# Digitalizador_RPi.net
KiCad netlist of a schematic drawn in Altium Designer
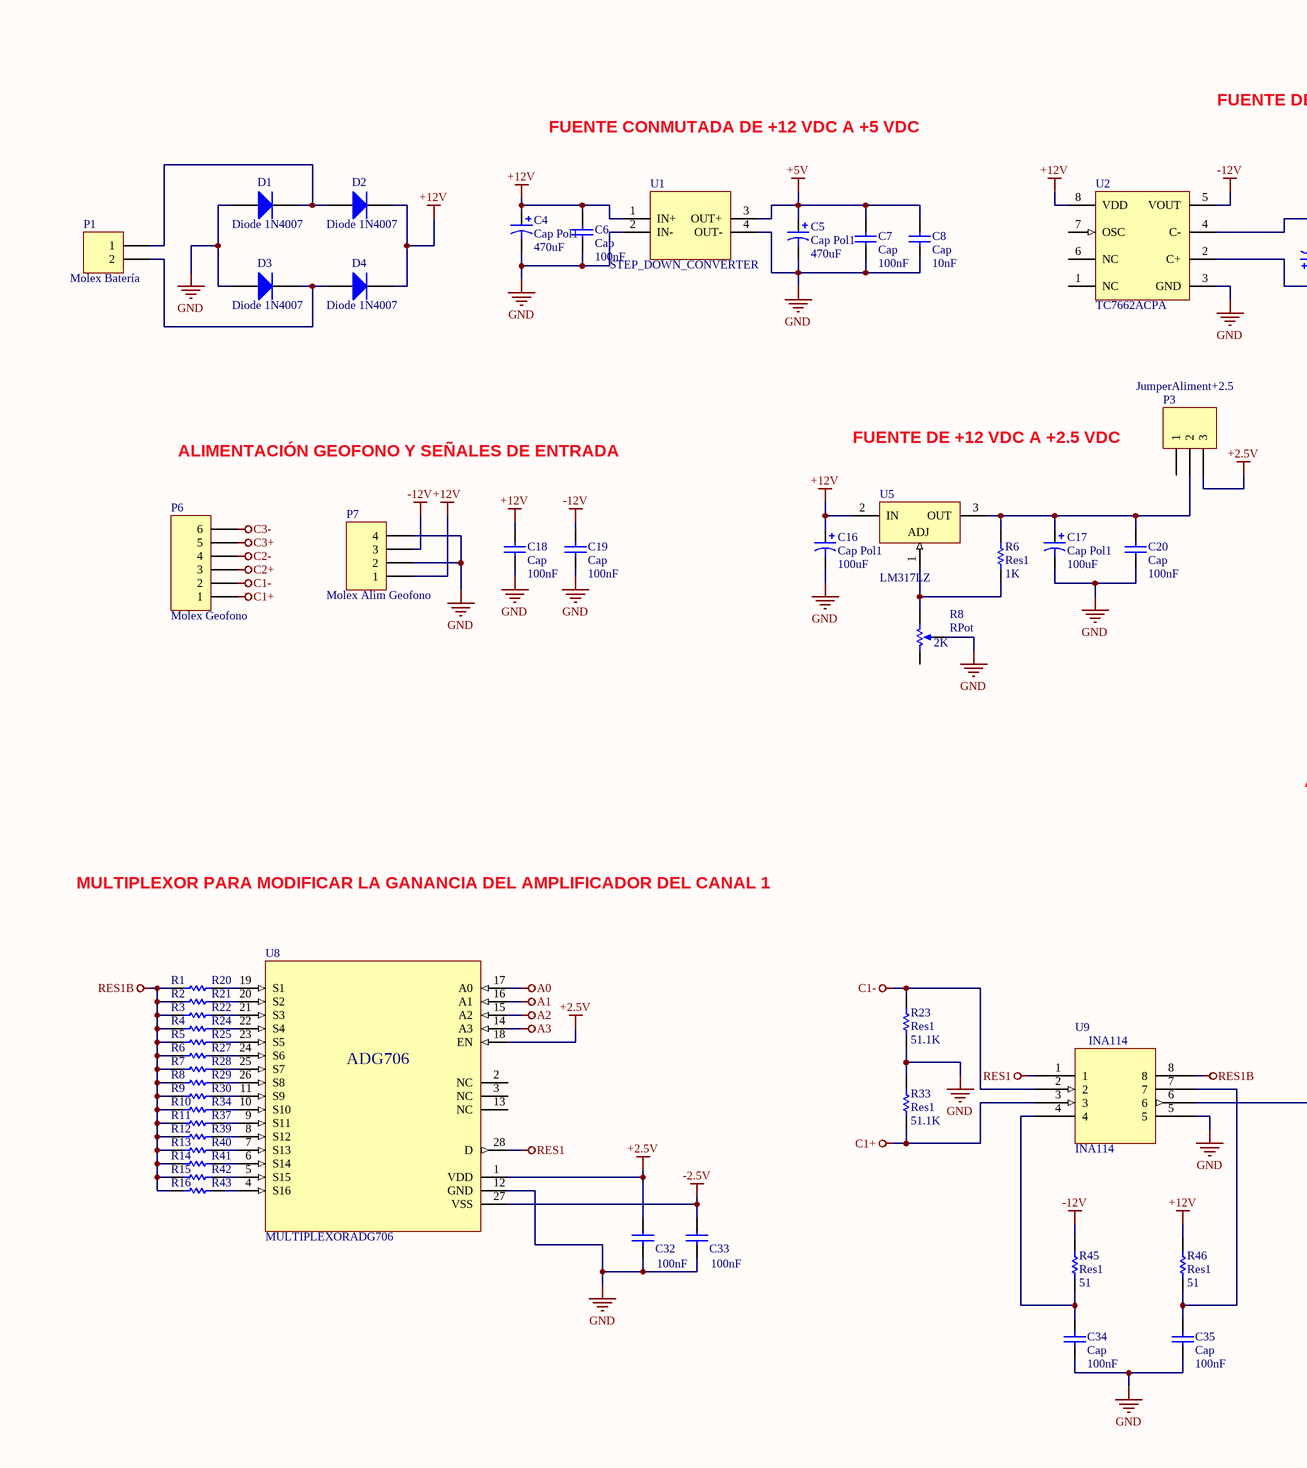
[diagram p0: Digitalizador_RPi.SchDoc, top left]
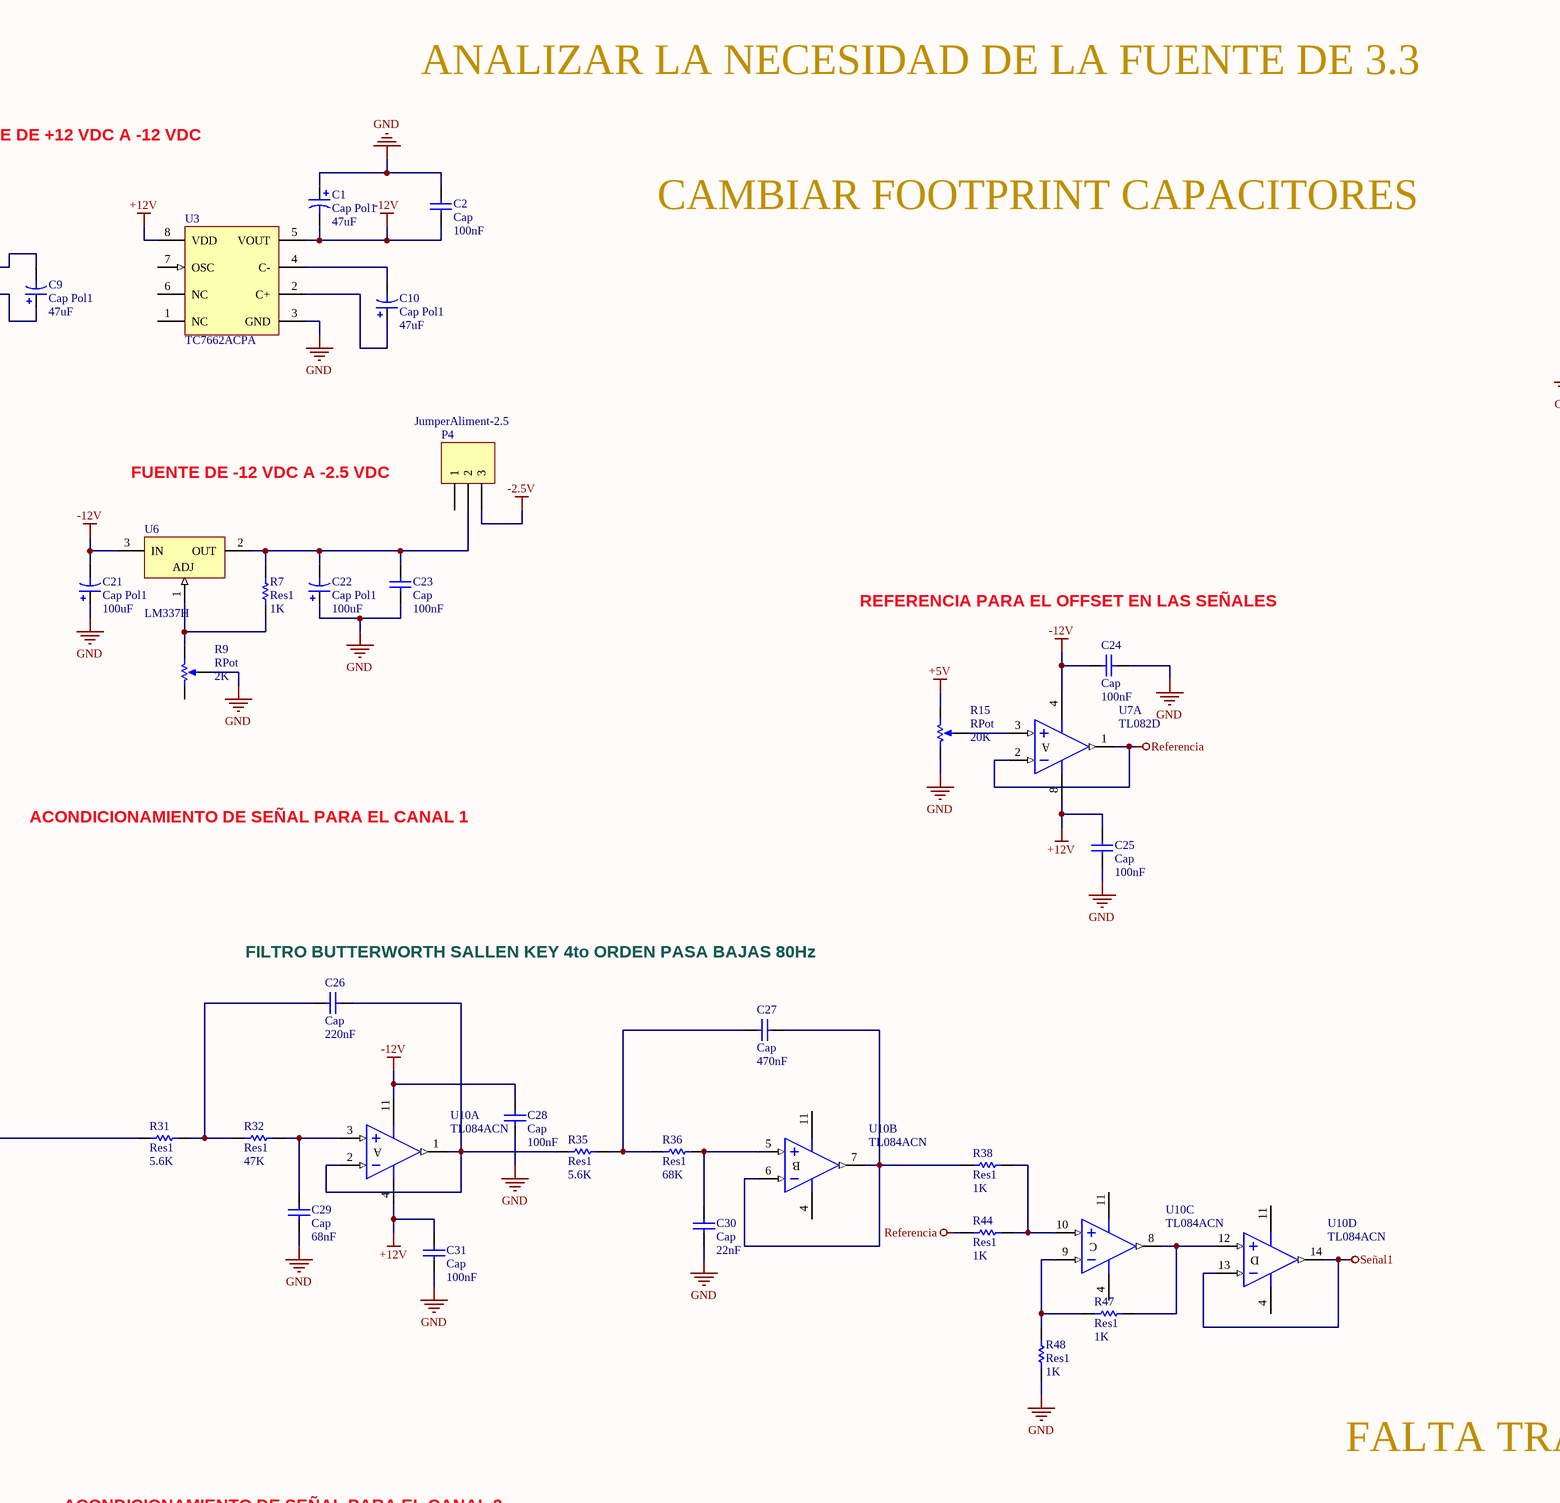
[diagram p1: Digitalizador_RPi.SchDoc, top middle]
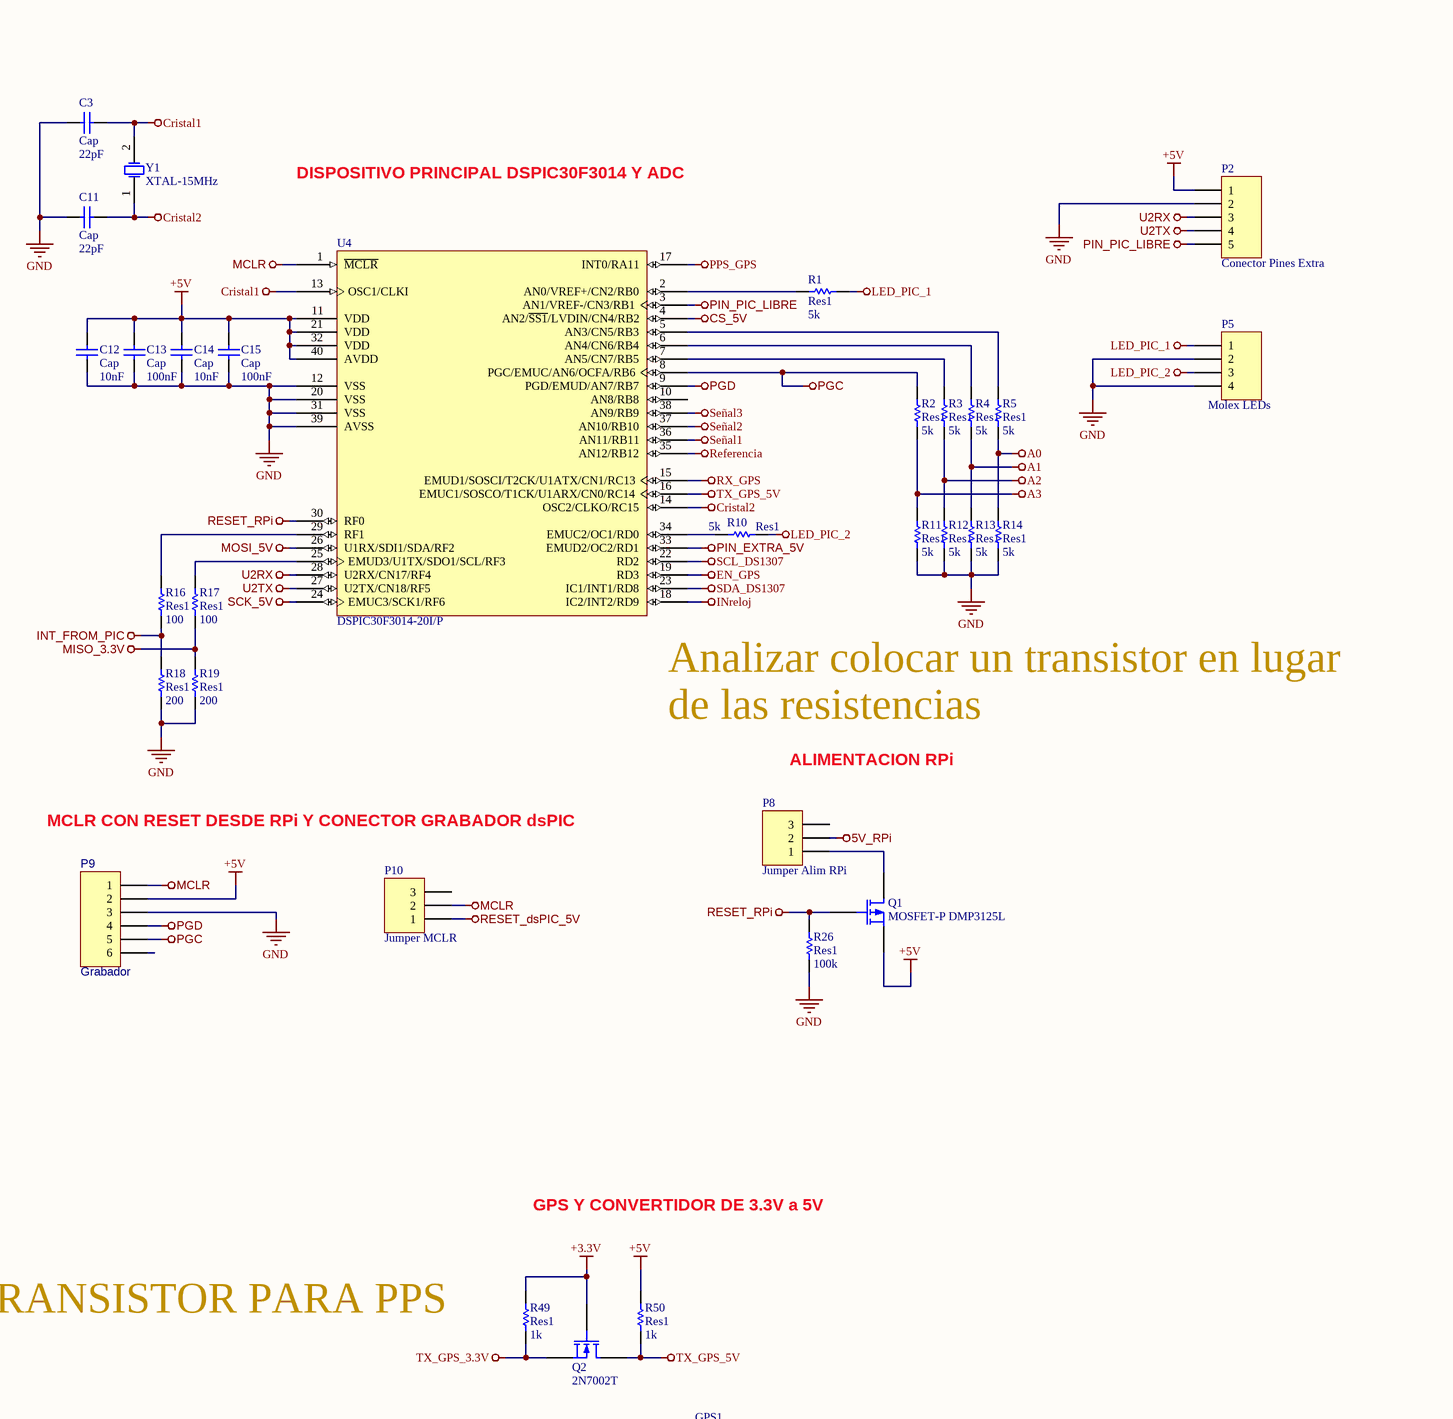
[diagram p2: Digitalizador_RPi.SchDoc, top right]
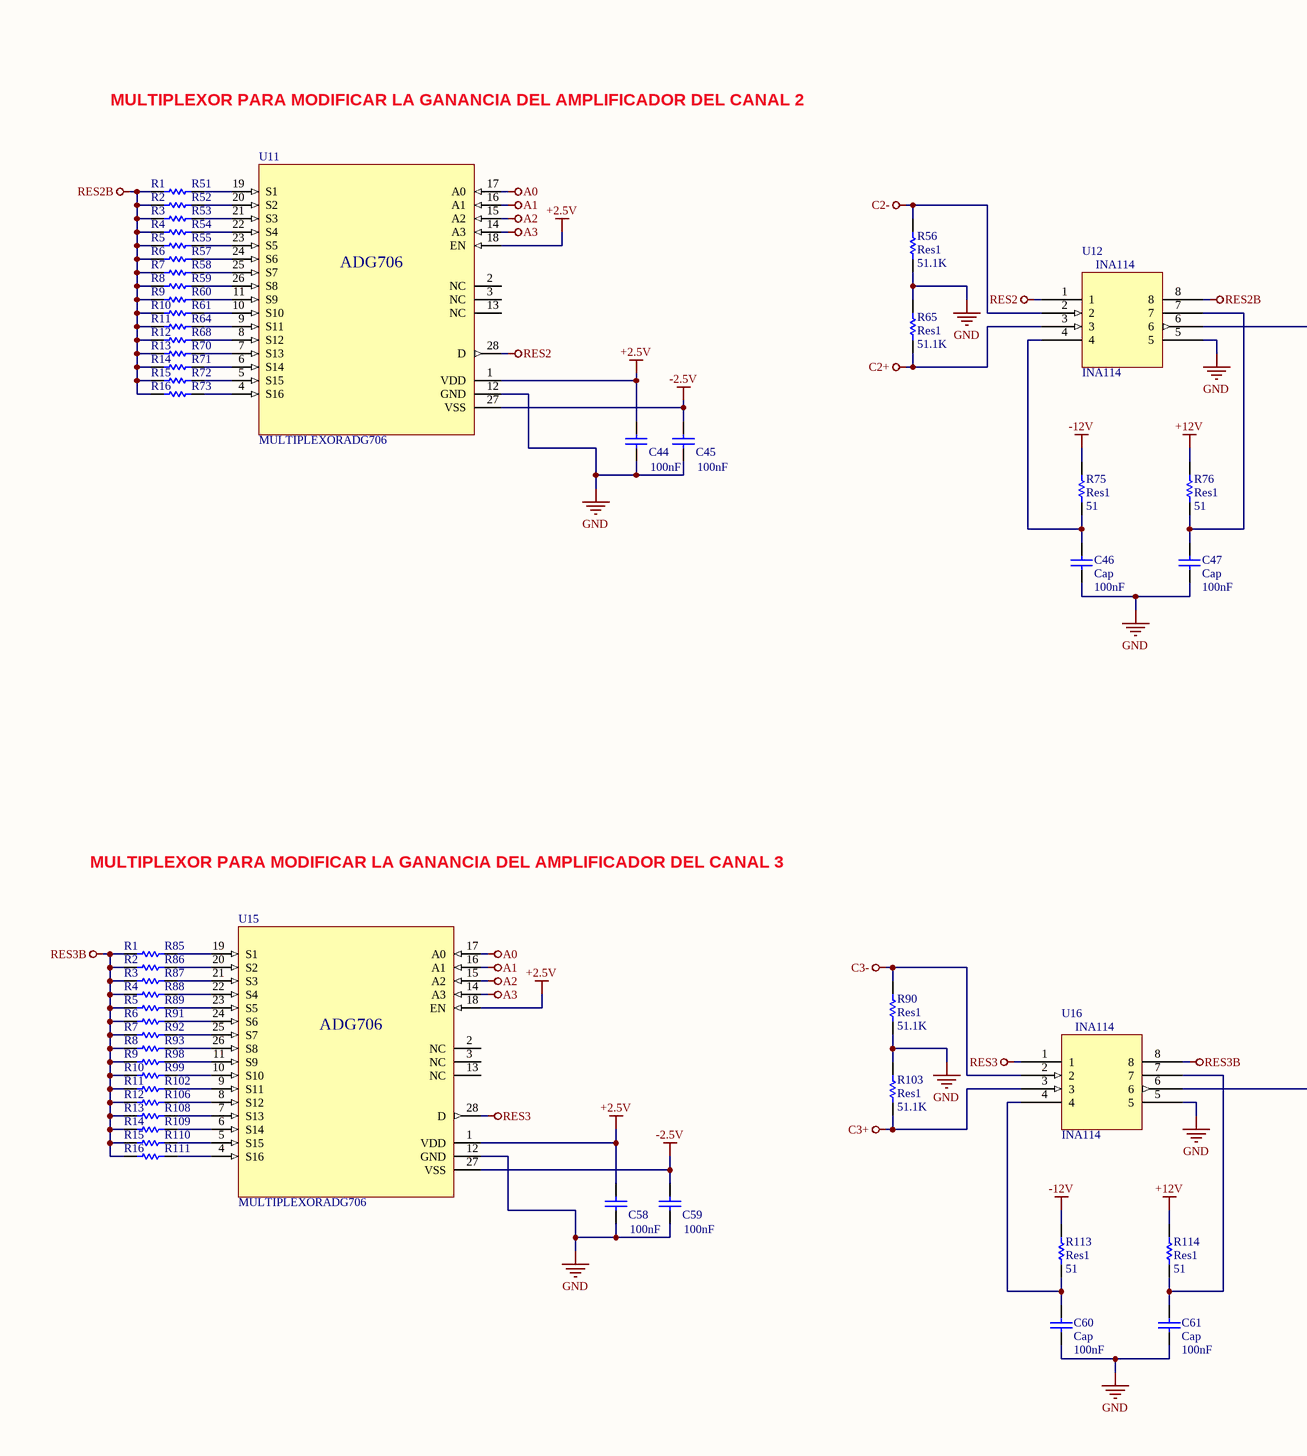
[diagram p3: Digitalizador_RPi.SchDoc, bottom left]
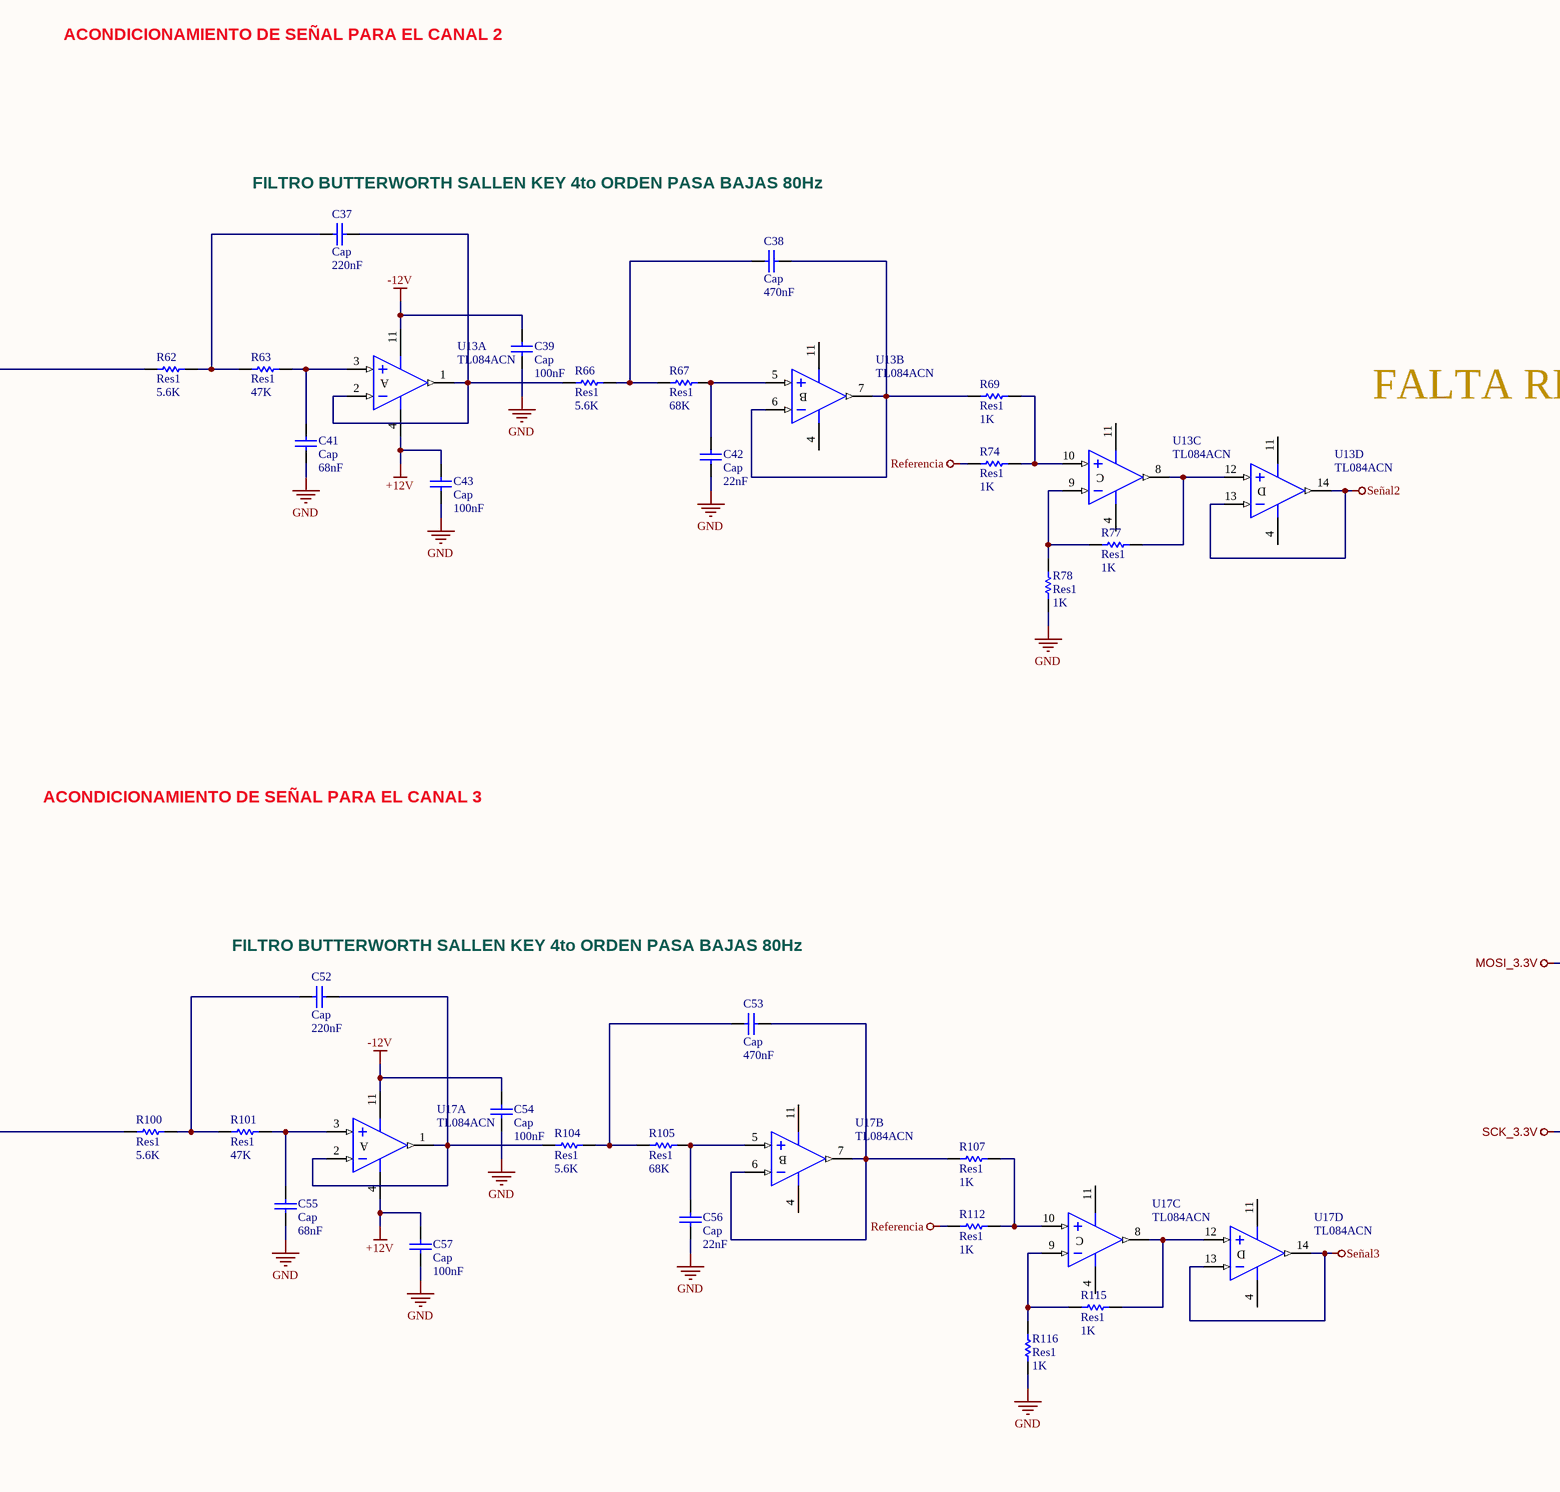
[diagram p4: Digitalizador_RPi.SchDoc, bottom middle]
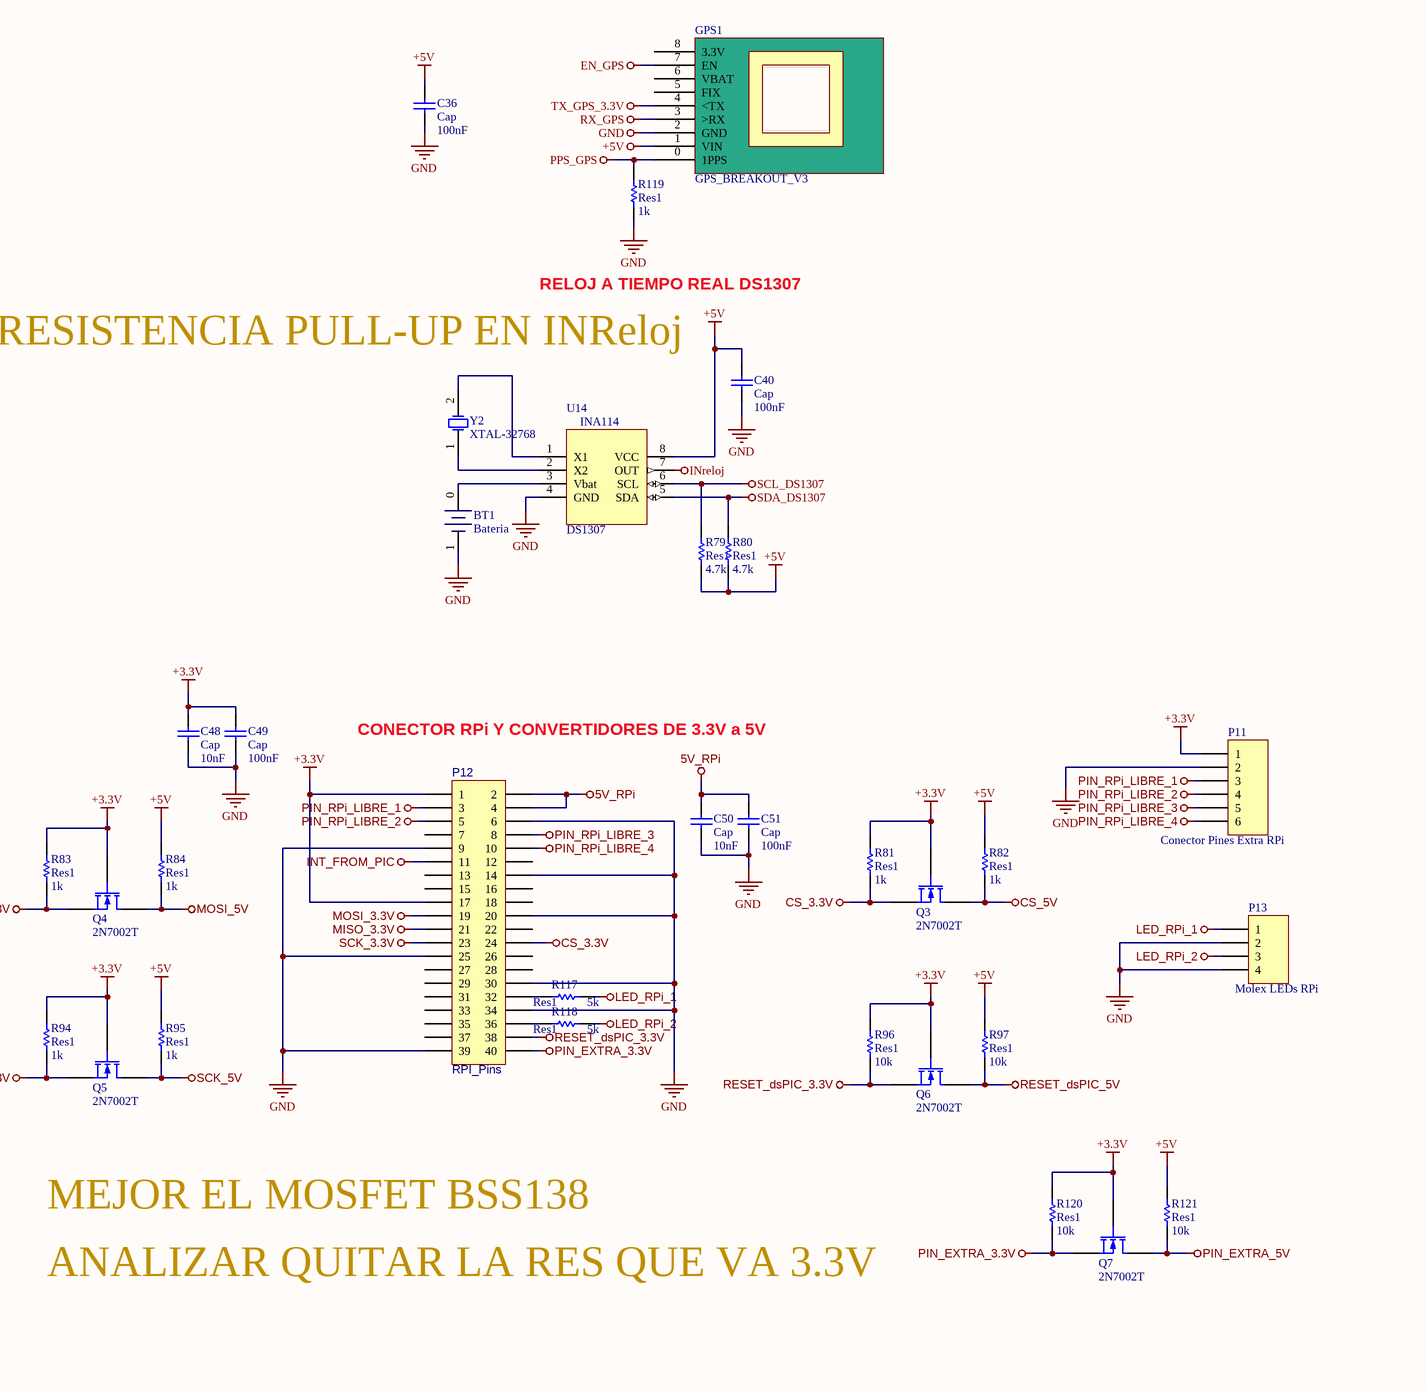
[diagram p5: Digitalizador_RPi.SchDoc, bottom right]

(export (version "E")
  (design (tool "Eeschema 10.0.6"))
  (components
    (comp (ref "BT1")
      (value "Bateria")
      (footprint "Bateria-DS1307")
      (libsource (lib "Libreria RSA") (part "BateriaDS1307"))
    )
    (comp (ref "C1")
      (value "Cap Pol1")
      (footprint "CAP_5.5MM")
      (description "Polarized Capacitor (Radial)")
      (fields (field (name "ALTIUM_VALUE") "47uF") (field (name "PUBLISHER") "Altium Limited"))
      (libsource (lib "Miscellaneous Devices") (part "Cap Pol1"))
    )
    (comp (ref "C2")
      (value "Cap")
      (footprint "0603")
      (description "Capacitor")
      (fields (field (name "ALTIUM_VALUE") "100nF") (field (name "PUBLISHER") "Altium Limited"))
      (libsource (lib "Miscellaneous Devices") (part "Cap"))
    )
    (comp (ref "C3")
      (value "Cap")
      (footprint "Resistencias:0603")
      (description "Capacitor")
      (fields (field (name "ALTIUM_VALUE") "22pF") (field (name "PUBLISHER") "Altium Limited"))
      (libsource (lib "Miscellaneous Devices") (part "Cap"))
    )
    (comp (ref "C4")
      (value "Cap Pol1")
      (footprint "CAP_8.5mm")
      (description "Polarized Capacitor (Radial)")
      (fields (field (name "ALTIUM_VALUE") "470uF") (field (name "PUBLISHER") "Altium Limited"))
      (libsource (lib "Miscellaneous Devices") (part "Cap Pol1"))
    )
    (comp (ref "C5")
      (value "Cap Pol1")
      (footprint "CAP_8.5mm")
      (description "Polarized Capacitor (Radial)")
      (fields (field (name "ALTIUM_VALUE") "470uF") (field (name "PUBLISHER") "Altium Limited"))
      (libsource (lib "Miscellaneous Devices") (part "Cap Pol1"))
    )
    (comp (ref "C6")
      (value "Cap")
      (footprint "0603")
      (description "Capacitor")
      (fields (field (name "ALTIUM_VALUE") "100nF") (field (name "PUBLISHER") "Altium Limited"))
      (libsource (lib "Miscellaneous Devices") (part "Cap"))
    )
    (comp (ref "C7")
      (value "Cap")
      (footprint "0603")
      (description "Capacitor")
      (fields (field (name "ALTIUM_VALUE") "100nF") (field (name "PUBLISHER") "Altium Limited"))
      (libsource (lib "Miscellaneous Devices") (part "Cap"))
    )
    (comp (ref "C8")
      (value "Cap")
      (footprint "0603")
      (description "Capacitor")
      (fields (field (name "ALTIUM_VALUE") "10nF") (field (name "PUBLISHER") "Altium Limited"))
      (libsource (lib "Miscellaneous Devices") (part "Cap"))
    )
    (comp (ref "C9")
      (value "Cap Pol1")
      (footprint "CAP_5.5MM")
      (description "Polarized Capacitor (Radial)")
      (fields (field (name "ALTIUM_VALUE") "47uF") (field (name "PUBLISHER") "Altium Limited"))
      (libsource (lib "Miscellaneous Devices") (part "Cap Pol1"))
    )
    (comp (ref "C10")
      (value "Cap Pol1")
      (footprint "CAP_5.5MM")
      (description "Polarized Capacitor (Radial)")
      (fields (field (name "ALTIUM_VALUE") "47uF") (field (name "PUBLISHER") "Altium Limited"))
      (libsource (lib "Miscellaneous Devices") (part "Cap Pol1"))
    )
    (comp (ref "C11")
      (value "Cap")
      (footprint "0603")
      (description "Capacitor")
      (fields (field (name "ALTIUM_VALUE") "22pF") (field (name "PUBLISHER") "Altium Limited"))
      (libsource (lib "Miscellaneous Devices") (part "Cap"))
    )
    (comp (ref "C12")
      (value "Cap")
      (footprint "0603")
      (description "Capacitor")
      (fields (field (name "ALTIUM_VALUE") "10nF") (field (name "PUBLISHER") "Altium Limited"))
      (libsource (lib "Miscellaneous Devices") (part "Cap"))
    )
    (comp (ref "C13")
      (value "Cap")
      (footprint "0603")
      (description "Capacitor")
      (fields (field (name "ALTIUM_VALUE") "100nF") (field (name "PUBLISHER") "Altium Limited"))
      (libsource (lib "Miscellaneous Devices") (part "Cap"))
    )
    (comp (ref "C14")
      (value "Cap")
      (footprint "0603")
      (description "Capacitor")
      (fields (field (name "ALTIUM_VALUE") "10nF") (field (name "PUBLISHER") "Altium Limited"))
      (libsource (lib "Miscellaneous Devices") (part "Cap"))
    )
    (comp (ref "C15")
      (value "Cap")
      (footprint "0603")
      (description "Capacitor")
      (fields (field (name "ALTIUM_VALUE") "100nF") (field (name "PUBLISHER") "Altium Limited"))
      (libsource (lib "Miscellaneous Devices") (part "Cap"))
    )
    (comp (ref "C16")
      (value "Cap Pol1")
      (footprint "CAP_5.5MM")
      (description "Polarized Capacitor (Radial)")
      (fields (field (name "ALTIUM_VALUE") "100uF") (field (name "PUBLISHER") "Altium Limited"))
      (libsource (lib "Miscellaneous Devices") (part "Cap Pol1"))
    )
    (comp (ref "C17")
      (value "Cap Pol1")
      (footprint "CAP_5.5MM")
      (description "Polarized Capacitor (Radial)")
      (fields (field (name "ALTIUM_VALUE") "100uF") (field (name "PUBLISHER") "Altium Limited"))
      (libsource (lib "Miscellaneous Devices") (part "Cap Pol1"))
    )
    (comp (ref "C18")
      (value "Cap")
      (footprint "0603")
      (description "Capacitor")
      (fields (field (name "ALTIUM_VALUE") "100nF") (field (name "PUBLISHER") "Altium Limited"))
      (libsource (lib "Miscellaneous Devices") (part "Cap"))
    )
    (comp (ref "C19")
      (value "Cap")
      (footprint "0603")
      (description "Capacitor")
      (fields (field (name "ALTIUM_VALUE") "100nF") (field (name "PUBLISHER") "Altium Limited"))
      (libsource (lib "Miscellaneous Devices") (part "Cap"))
    )
    (comp (ref "C20")
      (value "Cap")
      (footprint "0603")
      (description "Capacitor")
      (fields (field (name "ALTIUM_VALUE") "100nF") (field (name "PUBLISHER") "Altium Limited"))
      (libsource (lib "Miscellaneous Devices") (part "Cap"))
    )
    (comp (ref "C21")
      (value "Cap Pol1")
      (footprint "CAP_5.5MM")
      (description "Polarized Capacitor (Radial)")
      (fields (field (name "ALTIUM_VALUE") "100uF") (field (name "PUBLISHER") "Altium Limited"))
      (libsource (lib "Miscellaneous Devices") (part "Cap Pol1"))
    )
    (comp (ref "C22")
      (value "Cap Pol1")
      (footprint "CAP_5.5MM")
      (description "Polarized Capacitor (Radial)")
      (fields (field (name "ALTIUM_VALUE") "100uF") (field (name "PUBLISHER") "Altium Limited"))
      (libsource (lib "Miscellaneous Devices") (part "Cap Pol1"))
    )
    (comp (ref "C23")
      (value "Cap")
      (footprint "0603")
      (description "Capacitor")
      (fields (field (name "ALTIUM_VALUE") "100nF") (field (name "PUBLISHER") "Altium Limited"))
      (libsource (lib "Miscellaneous Devices") (part "Cap"))
    )
    (comp (ref "C24")
      (value "Cap")
      (footprint "0603")
      (description "Capacitor")
      (fields (field (name "ALTIUM_VALUE") "100nF") (field (name "PUBLISHER") "Altium Limited"))
      (libsource (lib "Miscellaneous Devices") (part "Cap"))
    )
    (comp (ref "C25")
      (value "Cap")
      (footprint "0603")
      (description "Capacitor")
      (fields (field (name "ALTIUM_VALUE") "100nF") (field (name "PUBLISHER") "Altium Limited"))
      (libsource (lib "Miscellaneous Devices") (part "Cap"))
    )
    (comp (ref "C26")
      (value "Cap")
      (footprint "RAD0.2")
      (description "Capacitor")
      (fields (field (name "ALTIUM_VALUE") "220nF") (field (name "PUBLISHER") "Altium Limited"))
      (libsource (lib "Miscellaneous Devices") (part "Cap"))
    )
    (comp (ref "C27")
      (value "Cap")
      (footprint "RAD0.2")
      (description "Capacitor")
      (fields (field (name "ALTIUM_VALUE") "470nF") (field (name "PUBLISHER") "Altium Limited"))
      (libsource (lib "Miscellaneous Devices") (part "Cap"))
    )
    (comp (ref "C28")
      (value "Cap")
      (footprint "0603")
      (description "Capacitor")
      (fields (field (name "ALTIUM_VALUE") "100nF") (field (name "PUBLISHER") "Altium Limited"))
      (libsource (lib "Miscellaneous Devices") (part "Cap"))
    )
    (comp (ref "C29")
      (value "Cap")
      (footprint "RAD0.2")
      (description "Capacitor")
      (fields (field (name "ALTIUM_VALUE") "68nF") (field (name "PUBLISHER") "Altium Limited"))
      (libsource (lib "Miscellaneous Devices") (part "Cap"))
    )
    (comp (ref "C30")
      (value "Cap")
      (footprint "RAD0.2")
      (description "Capacitor")
      (fields (field (name "ALTIUM_VALUE") "22nF") (field (name "PUBLISHER") "Altium Limited"))
      (libsource (lib "Miscellaneous Devices") (part "Cap"))
    )
    (comp (ref "C31")
      (value "Cap")
      (footprint "0603")
      (description "Capacitor")
      (fields (field (name "ALTIUM_VALUE") "100nF") (field (name "PUBLISHER") "Altium Limited"))
      (libsource (lib "Miscellaneous Devices") (part "Cap"))
    )
    (comp (ref "C32")
      (value "100nF")
      (footprint "0603")
      (description "Capacitor ceramico")
      (libsource (lib "Capacitores") (part "Capacitor ceramico"))
    )
    (comp (ref "C33")
      (value "100nF")
      (footprint "0603")
      (description "Capacitor ceramico")
      (libsource (lib "Capacitores") (part "Capacitor ceramico"))
    )
    (comp (ref "C34")
      (value "Cap")
      (footprint "0603")
      (description "Capacitor")
      (fields (field (name "ALTIUM_VALUE") "100nF") (field (name "PUBLISHER") "Altium Limited"))
      (libsource (lib "Miscellaneous Devices") (part "Cap"))
    )
    (comp (ref "C35")
      (value "Cap")
      (footprint "0603")
      (description "Capacitor")
      (fields (field (name "ALTIUM_VALUE") "100nF") (field (name "PUBLISHER") "Altium Limited"))
      (libsource (lib "Miscellaneous Devices") (part "Cap"))
    )
    (comp (ref "C36")
      (value "Cap")
      (footprint "0603")
      (description "Capacitor")
      (fields (field (name "ALTIUM_VALUE") "100nF") (field (name "PUBLISHER") "Altium Limited"))
      (libsource (lib "Miscellaneous Devices") (part "Cap"))
    )
    (comp (ref "C37")
      (value "Cap")
      (footprint "RAD0.2")
      (description "Capacitor")
      (fields (field (name "ALTIUM_VALUE") "220nF") (field (name "PUBLISHER") "Altium Limited"))
      (libsource (lib "Miscellaneous Devices") (part "Cap"))
    )
    (comp (ref "C38")
      (value "Cap")
      (footprint "RAD0.2")
      (description "Capacitor")
      (fields (field (name "ALTIUM_VALUE") "470nF") (field (name "PUBLISHER") "Altium Limited"))
      (libsource (lib "Miscellaneous Devices") (part "Cap"))
    )
    (comp (ref "C39")
      (value "Cap")
      (footprint "0603")
      (description "Capacitor")
      (fields (field (name "ALTIUM_VALUE") "100nF") (field (name "PUBLISHER") "Altium Limited"))
      (libsource (lib "Miscellaneous Devices") (part "Cap"))
    )
    (comp (ref "C40")
      (value "Cap")
      (footprint "0603")
      (description "Capacitor")
      (fields (field (name "ALTIUM_VALUE") "100nF") (field (name "PUBLISHER") "Altium Limited"))
      (libsource (lib "Miscellaneous Devices") (part "Cap"))
    )
    (comp (ref "C41")
      (value "Cap")
      (footprint "RAD0.2")
      (description "Capacitor")
      (fields (field (name "ALTIUM_VALUE") "68nF") (field (name "PUBLISHER") "Altium Limited"))
      (libsource (lib "Miscellaneous Devices") (part "Cap"))
    )
    (comp (ref "C42")
      (value "Cap")
      (footprint "RAD0.2")
      (description "Capacitor")
      (fields (field (name "ALTIUM_VALUE") "22nF") (field (name "PUBLISHER") "Altium Limited"))
      (libsource (lib "Miscellaneous Devices") (part "Cap"))
    )
    (comp (ref "C43")
      (value "Cap")
      (footprint "0603")
      (description "Capacitor")
      (fields (field (name "ALTIUM_VALUE") "100nF") (field (name "PUBLISHER") "Altium Limited"))
      (libsource (lib "Miscellaneous Devices") (part "Cap"))
    )
    (comp (ref "C44")
      (value "100nF")
      (footprint "0603")
      (description "Capacitor ceramico")
      (libsource (lib "Capacitores") (part "Capacitor ceramico"))
    )
    (comp (ref "C45")
      (value "100nF")
      (footprint "0603")
      (description "Capacitor ceramico")
      (libsource (lib "Capacitores") (part "Capacitor ceramico"))
    )
    (comp (ref "C46")
      (value "Cap")
      (footprint "0603")
      (description "Capacitor")
      (fields (field (name "ALTIUM_VALUE") "100nF") (field (name "PUBLISHER") "Altium Limited"))
      (libsource (lib "Miscellaneous Devices") (part "Cap"))
    )
    (comp (ref "C47")
      (value "Cap")
      (footprint "0603")
      (description "Capacitor")
      (fields (field (name "ALTIUM_VALUE") "100nF") (field (name "PUBLISHER") "Altium Limited"))
      (libsource (lib "Miscellaneous Devices") (part "Cap"))
    )
    (comp (ref "C48")
      (value "Cap")
      (footprint "0603")
      (description "Capacitor")
      (fields (field (name "ALTIUM_VALUE") "10nF") (field (name "PUBLISHER") "Altium Limited"))
      (libsource (lib "Miscellaneous Devices") (part "Cap"))
    )
    (comp (ref "C49")
      (value "Cap")
      (footprint "0603")
      (description "Capacitor")
      (fields (field (name "ALTIUM_VALUE") "100nF") (field (name "PUBLISHER") "Altium Limited"))
      (libsource (lib "Miscellaneous Devices") (part "Cap"))
    )
    (comp (ref "C50")
      (value "Cap")
      (footprint "0603")
      (description "Capacitor")
      (fields (field (name "ALTIUM_VALUE") "10nF") (field (name "PUBLISHER") "Altium Limited"))
      (libsource (lib "Miscellaneous Devices") (part "Cap"))
    )
    (comp (ref "C51")
      (value "Cap")
      (footprint "0603")
      (description "Capacitor")
      (fields (field (name "ALTIUM_VALUE") "100nF") (field (name "PUBLISHER") "Altium Limited"))
      (libsource (lib "Miscellaneous Devices") (part "Cap"))
    )
    (comp (ref "C52")
      (value "Cap")
      (footprint "RAD0.2")
      (description "Capacitor")
      (fields (field (name "ALTIUM_VALUE") "220nF") (field (name "PUBLISHER") "Altium Limited"))
      (libsource (lib "Miscellaneous Devices") (part "Cap"))
    )
    (comp (ref "C53")
      (value "Cap")
      (footprint "RAD0.2")
      (description "Capacitor")
      (fields (field (name "ALTIUM_VALUE") "470nF") (field (name "PUBLISHER") "Altium Limited"))
      (libsource (lib "Miscellaneous Devices") (part "Cap"))
    )
    (comp (ref "C54")
      (value "Cap")
      (footprint "0603")
      (description "Capacitor")
      (fields (field (name "ALTIUM_VALUE") "100nF") (field (name "PUBLISHER") "Altium Limited"))
      (libsource (lib "Miscellaneous Devices") (part "Cap"))
    )
    (comp (ref "C55")
      (value "Cap")
      (footprint "RAD0.2")
      (description "Capacitor")
      (fields (field (name "ALTIUM_VALUE") "68nF") (field (name "PUBLISHER") "Altium Limited"))
      (libsource (lib "Miscellaneous Devices") (part "Cap"))
    )
    (comp (ref "C56")
      (value "Cap")
      (footprint "RAD0.2")
      (description "Capacitor")
      (fields (field (name "ALTIUM_VALUE") "22nF") (field (name "PUBLISHER") "Altium Limited"))
      (libsource (lib "Miscellaneous Devices") (part "Cap"))
    )
    (comp (ref "C57")
      (value "Cap")
      (footprint "0603")
      (description "Capacitor")
      (fields (field (name "ALTIUM_VALUE") "100nF") (field (name "PUBLISHER") "Altium Limited"))
      (libsource (lib "Miscellaneous Devices") (part "Cap"))
    )
    (comp (ref "C58")
      (value "100nF")
      (footprint "0603")
      (description "Capacitor ceramico")
      (libsource (lib "Capacitores") (part "Capacitor ceramico"))
    )
    (comp (ref "C59")
      (value "100nF")
      (footprint "0603")
      (description "Capacitor ceramico")
      (libsource (lib "Capacitores") (part "Capacitor ceramico"))
    )
    (comp (ref "C60")
      (value "Cap")
      (footprint "0603")
      (description "Capacitor")
      (fields (field (name "ALTIUM_VALUE") "100nF") (field (name "PUBLISHER") "Altium Limited"))
      (libsource (lib "Miscellaneous Devices") (part "Cap"))
    )
    (comp (ref "C61")
      (value "Cap")
      (footprint "0603")
      (description "Capacitor")
      (fields (field (name "ALTIUM_VALUE") "100nF") (field (name "PUBLISHER") "Altium Limited"))
      (libsource (lib "Miscellaneous Devices") (part "Cap"))
    )
    (comp (ref "D1")
      (value "Diode 1N4007")
      (footprint "DIODE-0.4A")
      (description "1 Amp General Purpose Rectifier")
      (fields (field (name "PUBLISHER") "Altium Limited"))
      (libsource (lib "Miscellaneous Devices") (part "Diode 1N4007"))
    )
    (comp (ref "D2")
      (value "Diode 1N4007")
      (footprint "DIODE-0.4A")
      (description "1 Amp General Purpose Rectifier")
      (fields (field (name "PUBLISHER") "Altium Limited"))
      (libsource (lib "Miscellaneous Devices") (part "Diode 1N4007"))
    )
    (comp (ref "D3")
      (value "Diode 1N4007")
      (footprint "DIODE-0.4A")
      (description "1 Amp General Purpose Rectifier")
      (fields (field (name "PUBLISHER") "Altium Limited"))
      (libsource (lib "Miscellaneous Devices") (part "Diode 1N4007"))
    )
    (comp (ref "D4")
      (value "Diode 1N4007")
      (footprint "DIODE-0.4A")
      (description "1 Amp General Purpose Rectifier")
      (fields (field (name "PUBLISHER") "Altium Limited"))
      (libsource (lib "Miscellaneous Devices") (part "Diode 1N4007"))
    )
    (comp (ref "GPS1")
      (value "GPS_BREAKOUT_V3")
      (footprint "GPS_BREAKOUT_V3")
      (libsource (lib "LibreriaRSA") (part "GPS_BREAKOUT_V3"))
    )
    (comp (ref "P1")
      (value "Molex Batería")
      (footprint "MOLEX-2")
      (description "Header, 2-Pin")
      (fields (field (name "PUBLISHER") "Altium Limited"))
      (libsource (lib "Miscellaneous Connectors") (part "Header 2"))
    )
    (comp (ref "P2")
      (value "Conector Pines Extra")
      (footprint "HDR1X5")
      (description "Header, 5-Pin")
      (fields (field (name "PUBLISHER") "Altium Limited"))
      (libsource (lib "Miscellaneous Connectors") (part "Header 5"))
    )
    (comp (ref "P3")
      (value "JumperAliment+2.5")
      (footprint "SIP-1X3-M")
      (description "Header, 3-Pin")
      (fields (field (name "PUBLISHER") "Altium Limited"))
      (libsource (lib "Miscellaneous Connectors") (part "Header 3"))
    )
    (comp (ref "P4")
      (value "JumperAliment-2.5")
      (footprint "SIP-1X3-M")
      (description "Header, 3-Pin")
      (fields (field (name "PUBLISHER") "Altium Limited"))
      (libsource (lib "Miscellaneous Connectors") (part "Header 3"))
    )
    (comp (ref "P5")
      (value "Molex LEDs")
      (footprint "MOLEX-4")
      (description "Header, 4-Pin")
      (fields (field (name "PUBLISHER") "Altium Limited"))
      (libsource (lib "Miscellaneous Connectors") (part "Header 4"))
    )
    (comp (ref "P6")
      (value "Molex Geofono")
      (footprint "MOLEX-6")
      (description "Header, 6-Pin")
      (fields (field (name "PUBLISHER") "Altium Limited"))
      (libsource (lib "") (part "Header 6_2"))
    )
    (comp (ref "P7")
      (value "Molex Alim Geofono")
      (footprint "MOLEX-4")
      (description "Header, 4-Pin")
      (fields (field (name "PUBLISHER") "Altium Limited"))
      (libsource (lib "") (part "Header 4_1"))
    )
    (comp (ref "P8")
      (value "Jumper Alim RPi")
      (footprint "SIP-1X3-M")
      (description "Header, 3-Pin")
      (fields (field (name "PUBLISHER") "Altium Limited"))
      (libsource (lib "") (part "Header 3_1"))
    )
    (comp (ref "P9")
      (value "Grabador")
      (footprint "HDR1X6")
      (description "Header, 6-Pin")
      (fields (field (name "PUBLISHER") "Altium Limited"))
      (libsource (lib "Miscellaneous Connectors") (part "Header 6"))
    )
    (comp (ref "P10")
      (value "Jumper MCLR")
      (footprint "SIP-1X3-M")
      (description "Header, 3-Pin")
      (fields (field (name "PUBLISHER") "Altium Limited"))
      (libsource (lib "") (part "Header 3_1"))
    )
    (comp (ref "P11")
      (value "Conector Pines Extra RPi")
      (footprint "HDR1X6")
      (description "Header, 6-Pin")
      (fields (field (name "PUBLISHER") "Altium Limited"))
      (libsource (lib "") (part "Header 6_1"))
    )
    (comp (ref "P12")
      (value "RPI_Pins")
      (footprint "SIP-2X20-M")
      (description "Header, 20-Pin, Dual row")
      (fields (field (name "PUBLISHER") "Altium Limited"))
      (libsource (lib "Miscellaneous Connectors") (part "Header 20X2"))
    )
    (comp (ref "P13")
      (value "Molex LEDs RPi")
      (footprint "MOLEX-4")
      (description "Header, 4-Pin")
      (fields (field (name "PUBLISHER") "Altium Limited"))
      (libsource (lib "Miscellaneous Connectors") (part "Header 4"))
    )
    (comp (ref "Q1")
      (value "MOSFET-P DMP3125L")
      (footprint "SOT23-3L")
      (description "P-Channel MOSFET")
      (fields (field (name "PUBLISHER") "Altium Limited"))
      (libsource (lib "Miscellaneous Devices") (part "MOSFET-P"))
    )
    (comp (ref "Q2")
      (value "2N7002T")
      (footprint "SOT523")
      (libsource (lib "Transistores") (part "2N7002T-7-F"))
    )
    (comp (ref "Q3")
      (value "2N7002T")
      (footprint "SOT523")
      (libsource (lib "Transistores") (part "2N7002T-7-F"))
    )
    (comp (ref "Q4")
      (value "2N7002T")
      (footprint "SOT523")
      (libsource (lib "Transistores") (part "2N7002T-7-F"))
    )
    (comp (ref "Q5")
      (value "2N7002T")
      (footprint "SOT523")
      (libsource (lib "Transistores") (part "2N7002T-7-F"))
    )
    (comp (ref "Q6")
      (value "2N7002T")
      (footprint "SOT523")
      (libsource (lib "Transistores") (part "2N7002T-7-F"))
    )
    (comp (ref "Q7")
      (value "2N7002T")
      (footprint "SOT523")
      (libsource (lib "Transistores") (part "2N7002T-7-F"))
    )
    (comp (ref "R1")
      (value "Res1")
      (footprint "0805")
      (description "Resistor")
      (fields (field (name "ALTIUM_VALUE") "5k") (field (name "PUBLISHER") "Altium Limited"))
      (libsource (lib "Resistencias de carbon") (part "Res1"))
    )
    (comp (ref "R2")
      (value "Res1")
      (footprint "0805")
      (description "Resistor")
      (fields (field (name "ALTIUM_VALUE") "5k") (field (name "PUBLISHER") "Altium Limited"))
      (libsource (lib "Resistencias de carbon") (part "Res1"))
    )
    (comp (ref "R3")
      (value "Res1")
      (footprint "0805")
      (description "Resistor")
      (fields (field (name "ALTIUM_VALUE") "5k") (field (name "PUBLISHER") "Altium Limited"))
      (libsource (lib "Resistencias de carbon") (part "Res1"))
    )
    (comp (ref "R4")
      (value "Res1")
      (footprint "0805")
      (description "Resistor")
      (fields (field (name "ALTIUM_VALUE") "5k") (field (name "PUBLISHER") "Altium Limited"))
      (libsource (lib "Resistencias de carbon") (part "Res1"))
    )
    (comp (ref "R5")
      (value "Res1")
      (footprint "0805")
      (description "Resistor")
      (fields (field (name "ALTIUM_VALUE") "5k") (field (name "PUBLISHER") "Altium Limited"))
      (libsource (lib "Resistencias de carbon") (part "Res1"))
    )
    (comp (ref "R6")
      (value "Res1")
      (footprint "0805")
      (description "Resistor")
      (fields (field (name "ALTIUM_VALUE") "1K") (field (name "PUBLISHER") "Altium Limited"))
      (libsource (lib "Resistencias de carbon") (part "Res1"))
    )
    (comp (ref "R7")
      (value "Res1")
      (footprint "0805")
      (description "Resistor")
      (fields (field (name "ALTIUM_VALUE") "1K") (field (name "PUBLISHER") "Altium Limited"))
      (libsource (lib "Resistencias de carbon") (part "Res1"))
    )
    (comp (ref "R8")
      (value "RPot")
      (footprint "VR-5t")
      (description "Potentiometer")
      (fields (field (name "ALTIUM_VALUE") "2K") (field (name "PUBLISHER") "Altium Limited"))
      (libsource (lib "Miscellaneous Devices") (part "RPot"))
    )
    (comp (ref "R9")
      (value "RPot")
      (footprint "VR-5t")
      (description "Potentiometer")
      (fields (field (name "ALTIUM_VALUE") "2K") (field (name "PUBLISHER") "Altium Limited"))
      (libsource (lib "Miscellaneous Devices") (part "RPot"))
    )
    (comp (ref "R10")
      (value "Res1")
      (footprint "0805")
      (description "Resistor")
      (fields (field (name "ALTIUM_VALUE") "5k") (field (name "PUBLISHER") "Altium Limited"))
      (libsource (lib "Resistencias de carbon") (part "Res1"))
    )
    (comp (ref "R11")
      (value "Res1")
      (footprint "0805")
      (description "Resistor")
      (fields (field (name "ALTIUM_VALUE") "5k") (field (name "PUBLISHER") "Altium Limited"))
      (libsource (lib "Resistencias de carbon") (part "Res1"))
    )
    (comp (ref "R12")
      (value "Res1")
      (footprint "0805")
      (description "Resistor")
      (fields (field (name "ALTIUM_VALUE") "5k") (field (name "PUBLISHER") "Altium Limited"))
      (libsource (lib "Resistencias de carbon") (part "Res1"))
    )
    (comp (ref "R13")
      (value "Res1")
      (footprint "0805")
      (description "Resistor")
      (fields (field (name "ALTIUM_VALUE") "5k") (field (name "PUBLISHER") "Altium Limited"))
      (libsource (lib "Resistencias de carbon") (part "Res1"))
    )
    (comp (ref "R14")
      (value "Res1")
      (footprint "0805")
      (description "Resistor")
      (fields (field (name "ALTIUM_VALUE") "5k") (field (name "PUBLISHER") "Altium Limited"))
      (libsource (lib "Resistencias de carbon") (part "Res1"))
    )
    (comp (ref "R15")
      (value "RPot")
      (footprint "VR-5t")
      (description "Potentiometer")
      (fields (field (name "ALTIUM_VALUE") "20K") (field (name "PUBLISHER") "Altium Limited"))
      (libsource (lib "Miscellaneous Devices") (part "RPot"))
    )
    (comp (ref "R16")
      (value "Res1")
      (footprint "0805")
      (description "Resistor")
      (fields (field (name "ALTIUM_VALUE") "100") (field (name "PUBLISHER") "Altium Limited"))
      (libsource (lib "Resistencias de carbon") (part "Res1"))
    )
    (comp (ref "R17")
      (value "Res1")
      (footprint "0805")
      (description "Resistor")
      (fields (field (name "ALTIUM_VALUE") "100") (field (name "PUBLISHER") "Altium Limited"))
      (libsource (lib "Resistencias de carbon") (part "Res1"))
    )
    (comp (ref "R18")
      (value "Res1")
      (footprint "0805")
      (description "Resistor")
      (fields (field (name "ALTIUM_VALUE") "200") (field (name "PUBLISHER") "Altium Limited"))
      (libsource (lib "Resistencias de carbon") (part "Res1"))
    )
    (comp (ref "R19")
      (value "Res1")
      (footprint "0805")
      (description "Resistor")
      (fields (field (name "ALTIUM_VALUE") "200") (field (name "PUBLISHER") "Altium Limited"))
      (libsource (lib "Resistencias de carbon") (part "Res1"))
    )
    (comp (ref "R20")
      (value "R1")
      (footprint "0805")
      (description "Resistor")
      (fields (field (name "PUBLISHER") "Altium Limited"))
      (libsource (lib "Resistencias de carbon") (part "Res1"))
    )
    (comp (ref "R21")
      (value "R2")
      (footprint "0805")
      (description "Resistor")
      (fields (field (name "PUBLISHER") "Altium Limited"))
      (libsource (lib "Resistencias de carbon") (part "Res1"))
    )
    (comp (ref "R22")
      (value "R3")
      (footprint "0805")
      (description "Resistor")
      (fields (field (name "PUBLISHER") "Altium Limited"))
      (libsource (lib "Resistencias de carbon") (part "Res1"))
    )
    (comp (ref "R23")
      (value "Res1")
      (footprint "0805")
      (description "Resistor")
      (fields (field (name "ALTIUM_VALUE") "51.1K") (field (name "PUBLISHER") "Altium Limited"))
      (libsource (lib "Resistencias de carbon") (part "Res1"))
    )
    (comp (ref "R24")
      (value "R4")
      (footprint "0805")
      (description "Resistor")
      (fields (field (name "PUBLISHER") "Altium Limited"))
      (libsource (lib "Resistencias de carbon") (part "Res1"))
    )
    (comp (ref "R25")
      (value "R5")
      (footprint "0805")
      (description "Resistor")
      (fields (field (name "PUBLISHER") "Altium Limited"))
      (libsource (lib "Resistencias de carbon") (part "Res1"))
    )
    (comp (ref "R26")
      (value "Res1")
      (footprint "0805")
      (description "Resistor")
      (fields (field (name "ALTIUM_VALUE") "100k") (field (name "PUBLISHER") "Altium Limited"))
      (libsource (lib "Resistencias de carbon") (part "Res1"))
    )
    (comp (ref "R27")
      (value "R6")
      (footprint "0805")
      (description "Resistor")
      (fields (field (name "PUBLISHER") "Altium Limited"))
      (libsource (lib "Resistencias de carbon") (part "Res1"))
    )
    (comp (ref "R28")
      (value "R7")
      (footprint "0805")
      (description "Resistor")
      (fields (field (name "PUBLISHER") "Altium Limited"))
      (libsource (lib "Resistencias de carbon") (part "Res1"))
    )
    (comp (ref "R29")
      (value "R8")
      (footprint "0805")
      (description "Resistor")
      (fields (field (name "PUBLISHER") "Altium Limited"))
      (libsource (lib "Resistencias de carbon") (part "Res1"))
    )
    (comp (ref "R30")
      (value "R9")
      (footprint "0805")
      (description "Resistor")
      (fields (field (name "PUBLISHER") "Altium Limited"))
      (libsource (lib "Resistencias de carbon") (part "Res1"))
    )
    (comp (ref "R31")
      (value "Res1")
      (footprint "0805")
      (description "Resistor")
      (fields (field (name "ALTIUM_VALUE") "5.6K") (field (name "PUBLISHER") "Altium Limited"))
      (libsource (lib "Resistencias de carbon") (part "Res1"))
    )
    (comp (ref "R32")
      (value "Res1")
      (footprint "0805")
      (description "Resistor")
      (fields (field (name "ALTIUM_VALUE") "47K") (field (name "PUBLISHER") "Altium Limited"))
      (libsource (lib "Resistencias de carbon") (part "Res1"))
    )
    (comp (ref "R33")
      (value "Res1")
      (footprint "0805")
      (description "Resistor")
      (fields (field (name "ALTIUM_VALUE") "51.1K") (field (name "PUBLISHER") "Altium Limited"))
      (libsource (lib "Resistencias de carbon") (part "Res1"))
    )
    (comp (ref "R34")
      (value "R10")
      (footprint "0805")
      (description "Resistor")
      (fields (field (name "PUBLISHER") "Altium Limited"))
      (libsource (lib "Resistencias de carbon") (part "Res1"))
    )
    (comp (ref "R35")
      (value "Res1")
      (footprint "0805")
      (description "Resistor")
      (fields (field (name "ALTIUM_VALUE") "5.6K") (field (name "PUBLISHER") "Altium Limited"))
      (libsource (lib "Resistencias de carbon") (part "Res1"))
    )
    (comp (ref "R36")
      (value "Res1")
      (footprint "0805")
      (description "Resistor")
      (fields (field (name "ALTIUM_VALUE") "68K") (field (name "PUBLISHER") "Altium Limited"))
      (libsource (lib "Resistencias de carbon") (part "Res1"))
    )
    (comp (ref "R37")
      (value "R11")
      (footprint "0805")
      (description "Resistor")
      (fields (field (name "PUBLISHER") "Altium Limited"))
      (libsource (lib "Resistencias de carbon") (part "Res1"))
    )
    (comp (ref "R38")
      (value "Res1")
      (footprint "0805")
      (description "Resistor")
      (fields (field (name "ALTIUM_VALUE") "1K") (field (name "PUBLISHER") "Altium Limited"))
      (libsource (lib "Resistencias de carbon") (part "Res1"))
    )
    (comp (ref "R39")
      (value "R12")
      (footprint "0805")
      (description "Resistor")
      (fields (field (name "PUBLISHER") "Altium Limited"))
      (libsource (lib "Resistencias de carbon") (part "Res1"))
    )
    (comp (ref "R40")
      (value "R13")
      (footprint "0805")
      (description "Resistor")
      (fields (field (name "PUBLISHER") "Altium Limited"))
      (libsource (lib "Resistencias de carbon") (part "Res1"))
    )
    (comp (ref "R41")
      (value "R14")
      (footprint "0805")
      (description "Resistor")
      (fields (field (name "PUBLISHER") "Altium Limited"))
      (libsource (lib "Resistencias de carbon") (part "Res1"))
    )
    (comp (ref "R42")
      (value "R15")
      (footprint "0805")
      (description "Resistor")
      (fields (field (name "PUBLISHER") "Altium Limited"))
      (libsource (lib "Resistencias de carbon") (part "Res1"))
    )
    (comp (ref "R43")
      (value "R16")
      (footprint "0805")
      (description "Resistor")
      (fields (field (name "PUBLISHER") "Altium Limited"))
      (libsource (lib "Resistencias de carbon") (part "Res1"))
    )
    (comp (ref "R44")
      (value "Res1")
      (footprint "0805")
      (description "Resistor")
      (fields (field (name "ALTIUM_VALUE") "1K") (field (name "PUBLISHER") "Altium Limited"))
      (libsource (lib "Resistencias de carbon") (part "Res1"))
    )
    (comp (ref "R45")
      (value "Res1")
      (footprint "0805")
      (description "Resistor")
      (fields (field (name "ALTIUM_VALUE") "51") (field (name "PUBLISHER") "Altium Limited"))
      (libsource (lib "Resistencias de carbon") (part "Res1"))
    )
    (comp (ref "R46")
      (value "Res1")
      (footprint "0805")
      (description "Resistor")
      (fields (field (name "ALTIUM_VALUE") "51") (field (name "PUBLISHER") "Altium Limited"))
      (libsource (lib "Resistencias de carbon") (part "Res1"))
    )
    (comp (ref "R47")
      (value "Res1")
      (footprint "0805")
      (description "Resistor")
      (fields (field (name "ALTIUM_VALUE") "1K") (field (name "PUBLISHER") "Altium Limited"))
      (libsource (lib "Resistencias de carbon") (part "Res1"))
    )
    (comp (ref "R48")
      (value "Res1")
      (footprint "0805")
      (description "Resistor")
      (fields (field (name "ALTIUM_VALUE") "1K") (field (name "PUBLISHER") "Altium Limited"))
      (libsource (lib "Resistencias de carbon") (part "Res1"))
    )
    (comp (ref "R49")
      (value "Res1")
      (footprint "0805")
      (description "Resistor")
      (fields (field (name "ALTIUM_VALUE") "1k") (field (name "PUBLISHER") "Altium Limited"))
      (libsource (lib "Resistencias de carbon") (part "Res1"))
    )
    (comp (ref "R50")
      (value "Res1")
      (footprint "0805")
      (description "Resistor")
      (fields (field (name "ALTIUM_VALUE") "1k") (field (name "PUBLISHER") "Altium Limited"))
      (libsource (lib "Resistencias de carbon") (part "Res1"))
    )
    (comp (ref "R51")
      (value "R1")
      (footprint "0805")
      (description "Resistor")
      (fields (field (name "PUBLISHER") "Altium Limited"))
      (libsource (lib "Resistencias de carbon") (part "Res1"))
    )
    (comp (ref "R52")
      (value "R2")
      (footprint "0805")
      (description "Resistor")
      (fields (field (name "PUBLISHER") "Altium Limited"))
      (libsource (lib "Resistencias de carbon") (part "Res1"))
    )
    (comp (ref "R53")
      (value "R3")
      (footprint "0805")
      (description "Resistor")
      (fields (field (name "PUBLISHER") "Altium Limited"))
      (libsource (lib "Resistencias de carbon") (part "Res1"))
    )
    (comp (ref "R54")
      (value "R4")
      (footprint "0805")
      (description "Resistor")
      (fields (field (name "PUBLISHER") "Altium Limited"))
      (libsource (lib "Resistencias de carbon") (part "Res1"))
    )
    (comp (ref "R55")
      (value "R5")
      (footprint "0805")
      (description "Resistor")
      (fields (field (name "PUBLISHER") "Altium Limited"))
      (libsource (lib "Resistencias de carbon") (part "Res1"))
    )
    (comp (ref "R56")
      (value "Res1")
      (footprint "0805")
      (description "Resistor")
      (fields (field (name "ALTIUM_VALUE") "51.1K") (field (name "PUBLISHER") "Altium Limited"))
      (libsource (lib "Resistencias de carbon") (part "Res1"))
    )
    (comp (ref "R57")
      (value "R6")
      (footprint "0805")
      (description "Resistor")
      (fields (field (name "PUBLISHER") "Altium Limited"))
      (libsource (lib "Resistencias de carbon") (part "Res1"))
    )
    (comp (ref "R58")
      (value "R7")
      (footprint "0805")
      (description "Resistor")
      (fields (field (name "PUBLISHER") "Altium Limited"))
      (libsource (lib "Resistencias de carbon") (part "Res1"))
    )
    (comp (ref "R59")
      (value "R8")
      (footprint "0805")
      (description "Resistor")
      (fields (field (name "PUBLISHER") "Altium Limited"))
      (libsource (lib "Resistencias de carbon") (part "Res1"))
    )
    (comp (ref "R60")
      (value "R9")
      (footprint "0805")
      (description "Resistor")
      (fields (field (name "PUBLISHER") "Altium Limited"))
      (libsource (lib "Resistencias de carbon") (part "Res1"))
    )
    (comp (ref "R61")
      (value "R10")
      (footprint "0805")
      (description "Resistor")
      (fields (field (name "PUBLISHER") "Altium Limited"))
      (libsource (lib "Resistencias de carbon") (part "Res1"))
    )
    (comp (ref "R62")
      (value "Res1")
      (footprint "0805")
      (description "Resistor")
      (fields (field (name "ALTIUM_VALUE") "5.6K") (field (name "PUBLISHER") "Altium Limited"))
      (libsource (lib "Resistencias de carbon") (part "Res1"))
    )
    (comp (ref "R63")
      (value "Res1")
      (footprint "0805")
      (description "Resistor")
      (fields (field (name "ALTIUM_VALUE") "47K") (field (name "PUBLISHER") "Altium Limited"))
      (libsource (lib "Resistencias de carbon") (part "Res1"))
    )
    (comp (ref "R64")
      (value "R11")
      (footprint "0805")
      (description "Resistor")
      (fields (field (name "PUBLISHER") "Altium Limited"))
      (libsource (lib "Resistencias de carbon") (part "Res1"))
    )
    (comp (ref "R65")
      (value "Res1")
      (footprint "0805")
      (description "Resistor")
      (fields (field (name "ALTIUM_VALUE") "51.1K") (field (name "PUBLISHER") "Altium Limited"))
      (libsource (lib "Resistencias de carbon") (part "Res1"))
    )
    (comp (ref "R66")
      (value "Res1")
      (footprint "0805")
      (description "Resistor")
      (fields (field (name "ALTIUM_VALUE") "5.6K") (field (name "PUBLISHER") "Altium Limited"))
      (libsource (lib "Resistencias de carbon") (part "Res1"))
    )
    (comp (ref "R67")
      (value "Res1")
      (footprint "0805")
      (description "Resistor")
      (fields (field (name "ALTIUM_VALUE") "68K") (field (name "PUBLISHER") "Altium Limited"))
      (libsource (lib "Resistencias de carbon") (part "Res1"))
    )
    (comp (ref "R68")
      (value "R12")
      (footprint "0805")
      (description "Resistor")
      (fields (field (name "PUBLISHER") "Altium Limited"))
      (libsource (lib "Resistencias de carbon") (part "Res1"))
    )
    (comp (ref "R69")
      (value "Res1")
      (footprint "0805")
      (description "Resistor")
      (fields (field (name "ALTIUM_VALUE") "1K") (field (name "PUBLISHER") "Altium Limited"))
      (libsource (lib "Resistencias de carbon") (part "Res1"))
    )
    (comp (ref "R70")
      (value "R13")
      (footprint "0805")
      (description "Resistor")
      (fields (field (name "PUBLISHER") "Altium Limited"))
      (libsource (lib "Resistencias de carbon") (part "Res1"))
    )
    (comp (ref "R71")
      (value "R14")
      (footprint "0805")
      (description "Resistor")
      (fields (field (name "PUBLISHER") "Altium Limited"))
      (libsource (lib "Resistencias de carbon") (part "Res1"))
    )
    (comp (ref "R72")
      (value "R15")
      (footprint "0805")
      (description "Resistor")
      (fields (field (name "PUBLISHER") "Altium Limited"))
      (libsource (lib "Resistencias de carbon") (part "Res1"))
    )
    (comp (ref "R73")
      (value "R16")
      (footprint "0805")
      (description "Resistor")
      (fields (field (name "PUBLISHER") "Altium Limited"))
      (libsource (lib "Resistencias de carbon") (part "Res1"))
    )
    (comp (ref "R74")
      (value "Res1")
      (footprint "0805")
      (description "Resistor")
      (fields (field (name "ALTIUM_VALUE") "1K") (field (name "PUBLISHER") "Altium Limited"))
      (libsource (lib "Resistencias de carbon") (part "Res1"))
    )
    (comp (ref "R75")
      (value "Res1")
      (footprint "0805")
      (description "Resistor")
      (fields (field (name "ALTIUM_VALUE") "51") (field (name "PUBLISHER") "Altium Limited"))
      (libsource (lib "Resistencias de carbon") (part "Res1"))
    )
    (comp (ref "R76")
      (value "Res1")
      (footprint "0805")
      (description "Resistor")
      (fields (field (name "ALTIUM_VALUE") "51") (field (name "PUBLISHER") "Altium Limited"))
      (libsource (lib "Resistencias de carbon") (part "Res1"))
    )
    (comp (ref "R77")
      (value "Res1")
      (footprint "0805")
      (description "Resistor")
      (fields (field (name "ALTIUM_VALUE") "1K") (field (name "PUBLISHER") "Altium Limited"))
      (libsource (lib "Resistencias de carbon") (part "Res1"))
    )
    (comp (ref "R78")
      (value "Res1")
      (footprint "0805")
      (description "Resistor")
      (fields (field (name "ALTIUM_VALUE") "1K") (field (name "PUBLISHER") "Altium Limited"))
      (libsource (lib "Resistencias de carbon") (part "Res1"))
    )
    (comp (ref "R79")
      (value "Res1")
      (footprint "0805")
      (description "Resistor")
      (fields (field (name "ALTIUM_VALUE") "4.7k") (field (name "PUBLISHER") "Altium Limited"))
      (libsource (lib "Resistencias de carbon") (part "Res1"))
    )
    (comp (ref "R80")
      (value "Res1")
      (footprint "0805")
      (description "Resistor")
      (fields (field (name "ALTIUM_VALUE") "4.7k") (field (name "PUBLISHER") "Altium Limited"))
      (libsource (lib "Resistencias de carbon") (part "Res1"))
    )
    (comp (ref "R81")
      (value "Res1")
      (footprint "0805")
      (description "Resistor")
      (fields (field (name "ALTIUM_VALUE") "1k") (field (name "PUBLISHER") "Altium Limited"))
      (libsource (lib "Resistencias de carbon") (part "Res1"))
    )
    (comp (ref "R82")
      (value "Res1")
      (footprint "0805")
      (description "Resistor")
      (fields (field (name "ALTIUM_VALUE") "1k") (field (name "PUBLISHER") "Altium Limited"))
      (libsource (lib "Resistencias de carbon") (part "Res1"))
    )
    (comp (ref "R83")
      (value "Res1")
      (footprint "0805")
      (description "Resistor")
      (fields (field (name "ALTIUM_VALUE") "1k") (field (name "PUBLISHER") "Altium Limited"))
      (libsource (lib "Resistencias de carbon") (part "Res1"))
    )
    (comp (ref "R84")
      (value "Res1")
      (footprint "0805")
      (description "Resistor")
      (fields (field (name "ALTIUM_VALUE") "1k") (field (name "PUBLISHER") "Altium Limited"))
      (libsource (lib "Resistencias de carbon") (part "Res1"))
    )
    (comp (ref "R85")
      (value "R1")
      (footprint "0805")
      (description "Resistor")
      (fields (field (name "PUBLISHER") "Altium Limited"))
      (libsource (lib "Resistencias de carbon") (part "Res1"))
    )
    (comp (ref "R86")
      (value "R2")
      (footprint "0805")
      (description "Resistor")
      (fields (field (name "PUBLISHER") "Altium Limited"))
      (libsource (lib "Resistencias de carbon") (part "Res1"))
    )
    (comp (ref "R87")
      (value "R3")
      (footprint "0805")
      (description "Resistor")
      (fields (field (name "PUBLISHER") "Altium Limited"))
      (libsource (lib "Resistencias de carbon") (part "Res1"))
    )
    (comp (ref "R88")
      (value "R4")
      (footprint "0805")
      (description "Resistor")
      (fields (field (name "PUBLISHER") "Altium Limited"))
      (libsource (lib "Resistencias de carbon") (part "Res1"))
    )
    (comp (ref "R89")
      (value "R5")
      (footprint "0805")
      (description "Resistor")
      (fields (field (name "PUBLISHER") "Altium Limited"))
      (libsource (lib "Resistencias de carbon") (part "Res1"))
    )
    (comp (ref "R90")
      (value "Res1")
      (footprint "0805")
      (description "Resistor")
      (fields (field (name "ALTIUM_VALUE") "51.1K") (field (name "PUBLISHER") "Altium Limited"))
      (libsource (lib "Resistencias de carbon") (part "Res1"))
    )
    (comp (ref "R91")
      (value "R6")
      (footprint "0805")
      (description "Resistor")
      (fields (field (name "PUBLISHER") "Altium Limited"))
      (libsource (lib "Resistencias de carbon") (part "Res1"))
    )
    (comp (ref "R92")
      (value "R7")
      (footprint "0805")
      (description "Resistor")
      (fields (field (name "PUBLISHER") "Altium Limited"))
      (libsource (lib "Resistencias de carbon") (part "Res1"))
    )
    (comp (ref "R93")
      (value "R8")
      (footprint "0805")
      (description "Resistor")
      (fields (field (name "PUBLISHER") "Altium Limited"))
      (libsource (lib "Resistencias de carbon") (part "Res1"))
    )
    (comp (ref "R94")
      (value "Res1")
      (footprint "0805")
      (description "Resistor")
      (fields (field (name "ALTIUM_VALUE") "1k") (field (name "PUBLISHER") "Altium Limited"))
      (libsource (lib "Resistencias de carbon") (part "Res1"))
    )
    (comp (ref "R95")
      (value "Res1")
      (footprint "0805")
      (description "Resistor")
      (fields (field (name "ALTIUM_VALUE") "1k") (field (name "PUBLISHER") "Altium Limited"))
      (libsource (lib "Resistencias de carbon") (part "Res1"))
    )
    (comp (ref "R96")
      (value "Res1")
      (footprint "0805")
      (description "Resistor")
      (fields (field (name "ALTIUM_VALUE") "10k") (field (name "PUBLISHER") "Altium Limited"))
      (libsource (lib "Resistencias de carbon") (part "Res1"))
    )
    (comp (ref "R97")
      (value "Res1")
      (footprint "0805")
      (description "Resistor")
      (fields (field (name "ALTIUM_VALUE") "10k") (field (name "PUBLISHER") "Altium Limited"))
      (libsource (lib "Resistencias de carbon") (part "Res1"))
    )
    (comp (ref "R98")
      (value "R9")
      (footprint "0805")
      (description "Resistor")
      (fields (field (name "PUBLISHER") "Altium Limited"))
      (libsource (lib "Resistencias de carbon") (part "Res1"))
    )
    (comp (ref "R99")
      (value "R10")
      (footprint "0805")
      (description "Resistor")
      (fields (field (name "PUBLISHER") "Altium Limited"))
      (libsource (lib "Resistencias de carbon") (part "Res1"))
    )
    (comp (ref "R100")
      (value "Res1")
      (footprint "0805")
      (description "Resistor")
      (fields (field (name "ALTIUM_VALUE") "5.6K") (field (name "PUBLISHER") "Altium Limited"))
      (libsource (lib "Resistencias de carbon") (part "Res1"))
    )
    (comp (ref "R101")
      (value "Res1")
      (footprint "0805")
      (description "Resistor")
      (fields (field (name "ALTIUM_VALUE") "47K") (field (name "PUBLISHER") "Altium Limited"))
      (libsource (lib "Resistencias de carbon") (part "Res1"))
    )
    (comp (ref "R102")
      (value "R11")
      (footprint "0805")
      (description "Resistor")
      (fields (field (name "PUBLISHER") "Altium Limited"))
      (libsource (lib "Resistencias de carbon") (part "Res1"))
    )
    (comp (ref "R103")
      (value "Res1")
      (footprint "0805")
      (description "Resistor")
      (fields (field (name "ALTIUM_VALUE") "51.1K") (field (name "PUBLISHER") "Altium Limited"))
      (libsource (lib "Resistencias de carbon") (part "Res1"))
    )
    (comp (ref "R104")
      (value "Res1")
      (footprint "0805")
      (description "Resistor")
      (fields (field (name "ALTIUM_VALUE") "5.6K") (field (name "PUBLISHER") "Altium Limited"))
      (libsource (lib "Resistencias de carbon") (part "Res1"))
    )
    (comp (ref "R105")
      (value "Res1")
      (footprint "0805")
      (description "Resistor")
      (fields (field (name "ALTIUM_VALUE") "68K") (field (name "PUBLISHER") "Altium Limited"))
      (libsource (lib "Resistencias de carbon") (part "Res1"))
    )
    (comp (ref "R106")
      (value "R12")
      (footprint "0805")
      (description "Resistor")
      (fields (field (name "PUBLISHER") "Altium Limited"))
      (libsource (lib "Resistencias de carbon") (part "Res1"))
    )
    (comp (ref "R107")
      (value "Res1")
      (footprint "0805")
      (description "Resistor")
      (fields (field (name "ALTIUM_VALUE") "1K") (field (name "PUBLISHER") "Altium Limited"))
      (libsource (lib "Resistencias de carbon") (part "Res1"))
    )
    (comp (ref "R108")
      (value "R13")
      (footprint "0805")
      (description "Resistor")
      (fields (field (name "PUBLISHER") "Altium Limited"))
      (libsource (lib "Resistencias de carbon") (part "Res1"))
    )
    (comp (ref "R109")
      (value "R14")
      (footprint "0805")
      (description "Resistor")
      (fields (field (name "PUBLISHER") "Altium Limited"))
      (libsource (lib "Resistencias de carbon") (part "Res1"))
    )
    (comp (ref "R110")
      (value "R15")
      (footprint "0805")
      (description "Resistor")
      (fields (field (name "PUBLISHER") "Altium Limited"))
      (libsource (lib "Resistencias de carbon") (part "Res1"))
    )
    (comp (ref "R111")
      (value "R16")
      (footprint "0805")
      (description "Resistor")
      (fields (field (name "PUBLISHER") "Altium Limited"))
      (libsource (lib "Resistencias de carbon") (part "Res1"))
    )
    (comp (ref "R112")
      (value "Res1")
      (footprint "0805")
      (description "Resistor")
      (fields (field (name "ALTIUM_VALUE") "1K") (field (name "PUBLISHER") "Altium Limited"))
      (libsource (lib "Resistencias de carbon") (part "Res1"))
    )
    (comp (ref "R113")
      (value "Res1")
      (footprint "0805")
      (description "Resistor")
      (fields (field (name "ALTIUM_VALUE") "51") (field (name "PUBLISHER") "Altium Limited"))
      (libsource (lib "Resistencias de carbon") (part "Res1"))
    )
    (comp (ref "R114")
      (value "Res1")
      (footprint "0805")
      (description "Resistor")
      (fields (field (name "ALTIUM_VALUE") "51") (field (name "PUBLISHER") "Altium Limited"))
      (libsource (lib "Resistencias de carbon") (part "Res1"))
    )
    (comp (ref "R115")
      (value "Res1")
      (footprint "0805")
      (description "Resistor")
      (fields (field (name "ALTIUM_VALUE") "1K") (field (name "PUBLISHER") "Altium Limited"))
      (libsource (lib "Resistencias de carbon") (part "Res1"))
    )
    (comp (ref "R116")
      (value "Res1")
      (footprint "0805")
      (description "Resistor")
      (fields (field (name "ALTIUM_VALUE") "1K") (field (name "PUBLISHER") "Altium Limited"))
      (libsource (lib "Resistencias de carbon") (part "Res1"))
    )
    (comp (ref "R117")
      (value "Res1")
      (footprint "0805")
      (description "Resistor")
      (fields (field (name "ALTIUM_VALUE") "5k") (field (name "PUBLISHER") "Altium Limited"))
      (libsource (lib "Resistencias de carbon") (part "Res1"))
    )
    (comp (ref "R118")
      (value "Res1")
      (footprint "0805")
      (description "Resistor")
      (fields (field (name "ALTIUM_VALUE") "5k") (field (name "PUBLISHER") "Altium Limited"))
      (libsource (lib "Resistencias de carbon") (part "Res1"))
    )
    (comp (ref "R119")
      (value "Res1")
      (footprint "0805")
      (description "Resistor")
      (fields (field (name "ALTIUM_VALUE") "1k") (field (name "PUBLISHER") "Altium Limited"))
      (libsource (lib "Resistencias de carbon") (part "Res1"))
    )
    (comp (ref "R120")
      (value "Res1")
      (footprint "0805")
      (description "Resistor")
      (fields (field (name "ALTIUM_VALUE") "10k") (field (name "PUBLISHER") "Altium Limited"))
      (libsource (lib "Resistencias de carbon") (part "Res1"))
    )
    (comp (ref "R121")
      (value "Res1")
      (footprint "0805")
      (description "Resistor")
      (fields (field (name "ALTIUM_VALUE") "10k") (field (name "PUBLISHER") "Altium Limited"))
      (libsource (lib "Resistencias de carbon") (part "Res1"))
    )
    (comp (ref "U1")
      (value "STEP_DOWN_CONVERTER")
      (footprint "STEP_DOWN_CONVERTER")
      (libsource (lib "LibreriaRSA") (part "STEP_DOWN_CONVERTER"))
    )
    (comp (ref "U2")
      (value "TC7662ACPA")
      (footprint "DIP-8")
      (description "Super Charge Pump DC-to-DC Voltage Converter, 12kHz, 8-Pin PDIP, Commercial Temperature")
      (fields (field (name "PUBLISHER") "Altium Limited"))
      (libsource (lib "Microchip Power Mgt Charge Pump") (part "TC7662ACPA"))
    )
    (comp (ref "U3")
      (value "TC7662ACPA")
      (footprint "DIP-8")
      (description "Super Charge Pump DC-to-DC Voltage Converter, 12kHz, 8-Pin PDIP, Commercial Temperature")
      (fields (field (name "PUBLISHER") "Altium Limited"))
      (libsource (lib "Microchip Power Mgt Charge Pump") (part "TC7662ACPA"))
    )
    (comp (ref "U4")
      (value "DSPIC30F3014-20I/P")
      (footprint "DIP-40")
      (fields (field (name "PUBLISHER") "Altium Limited"))
      (libsource (lib "Microchip DSC 16-Bit dsPIC30F") (part "DSPIC30F3014-20I/P"))
    )
    (comp (ref "U5")
      (value "LM317LZ")
      (footprint "TO-92B_2")
      (description "Low-Current 1.2V to 37V Voltage Regulator")
      (fields (field (name "PUBLISHER") "Altium Limited"))
      (libsource (lib "ST Power Mgt Voltage Regulator") (part "LM317LZ"))
    )
    (comp (ref "U6")
      (value "LM337H")
      (footprint "TO-220V")
      (description "Three-Terminal Adjustable Negative Voltage Regulator")
      (fields (field (name "PUBLISHER") "Altium Limited"))
      (libsource (lib "ST Power Mgt Voltage Regulator") (part "LM337H"))
    )
    (comp (ref "U7")
      (value "TL082D")
      (footprint "DIP-8")
      (description "JFET-Input Operational Amplifier")
      (fields (field (name "PUBLISHER") "Altium Limited"))
      (libsource (lib "TI Operational Amplifier") (part "TL082D"))
    )
    (comp (ref "U8")
      (value "MULTIPLEXORADG706")
      (footprint "MULTIPLEXORADG706SMD")
      (libsource (lib "Libreria RSA") (part "MULTIPLEXORADG706"))
    )
    (comp (ref "U9") (value "INA114") (footprint "DIP-8") (libsource (lib "Libreria RSA") (part "INA114")))
    (comp (ref "U10")
      (value "TL084ACN")
      (footprint "SOIC-14")
      (description "General-Purpose J-FET Quad Operational Amplifier")
      (fields (field (name "PUBLISHER") "Altium Limited"))
      (libsource (lib "ST Operational Amplifier") (part "TL084ACN"))
    )
    (comp (ref "U11")
      (value "MULTIPLEXORADG706")
      (footprint "MULTIPLEXORADG706SMD")
      (libsource (lib "Libreria RSA") (part "MULTIPLEXORADG706"))
    )
    (comp (ref "U12") (value "INA114") (footprint "DIP-8") (libsource (lib "Libreria RSA") (part "INA114")))
    (comp (ref "U13")
      (value "TL084ACN")
      (footprint "SOIC-14")
      (description "General-Purpose J-FET Quad Operational Amplifier")
      (fields (field (name "PUBLISHER") "Altium Limited"))
      (libsource (lib "ST Operational Amplifier") (part "TL084ACN"))
    )
    (comp (ref "U14") (value "DS1307") (footprint "DIP-8") (libsource (lib "Libreria RSA") (part "DS1307")))
    (comp (ref "U15")
      (value "MULTIPLEXORADG706")
      (footprint "MULTIPLEXORADG706SMD")
      (libsource (lib "Libreria RSA") (part "MULTIPLEXORADG706"))
    )
    (comp (ref "U16") (value "INA114") (footprint "DIP-8") (libsource (lib "Libreria RSA") (part "INA114")))
    (comp (ref "U17")
      (value "TL084ACN")
      (footprint "SOIC-14")
      (description "General-Purpose J-FET Quad Operational Amplifier")
      (fields (field (name "PUBLISHER") "Altium Limited"))
      (libsource (lib "ST Operational Amplifier") (part "TL084ACN"))
    )
    (comp (ref "Y1")
      (value "XTAL-15MHz")
      (footprint "CRISTAL10MHz")
      (description "Crystal Oscillator")
      (fields (field (name "PUBLISHER") "Altium Limited"))
      (libsource (lib "Miscellaneous Devices") (part "XTAL"))
    )
    (comp (ref "Y2")
      (value "XTAL-32768")
      (footprint "CRISTAL32768")
      (description "Crystal Oscillator")
      (fields (field (name "PUBLISHER") "Altium Limited"))
      (libsource (lib "Miscellaneous Devices") (part "XTAL"))
    )
  )
  (nets
    (net (code "1") (name "+2.5V") (class "Default")
      (node (ref "C32") (pin "2") (pinfunction "2_2") (pintype "passive"))
      (node (ref "C44") (pin "2") (pinfunction "2_2") (pintype "passive"))
      (node (ref "C58") (pin "2") (pinfunction "2_2") (pintype "passive"))
      (node (ref "P3") (pin "3") (pinfunction "3_3") (pintype "passive"))
      (node (ref "U11") (pin "1") (pinfunction "VDD_1") (pintype "power_in"))
      (node (ref "U11") (pin "18") (pinfunction "EN_18") (pintype "input"))
      (node (ref "U15") (pin "1") (pinfunction "VDD_1") (pintype "power_in"))
      (node (ref "U15") (pin "18") (pinfunction "EN_18") (pintype "input"))
      (node (ref "U8") (pin "1") (pinfunction "VDD_1") (pintype "power_in"))
      (node (ref "U8") (pin "18") (pinfunction "EN_18") (pintype "input"))
    )
    (net (code "2") (name "+3.3V") (class "Default")
      (node (ref "C48") (pin "2") (pinfunction "2_2") (pintype "passive"))
      (node (ref "C49") (pin "2") (pinfunction "2_2") (pintype "passive"))
      (node (ref "P11") (pin "1") (pinfunction "1_1") (pintype "passive"))
      (node (ref "P12") (pin "1") (pinfunction "1_1") (pintype "passive"))
      (node (ref "P12") (pin "17") (pinfunction "17_17") (pintype "passive"))
      (node (ref "Q2") (pin "1") (pinfunction "G_1") (pintype "passive"))
      (node (ref "Q3") (pin "1") (pinfunction "G_1") (pintype "passive"))
      (node (ref "Q4") (pin "1") (pinfunction "G_1") (pintype "passive"))
      (node (ref "Q5") (pin "1") (pinfunction "G_1") (pintype "passive"))
      (node (ref "Q6") (pin "1") (pinfunction "G_1") (pintype "passive"))
      (node (ref "Q7") (pin "1") (pinfunction "G_1") (pintype "passive"))
      (node (ref "R120") (pin "2") (pinfunction "2_2") (pintype "passive"))
      (node (ref "R49") (pin "2") (pinfunction "2_2") (pintype "passive"))
      (node (ref "R81") (pin "2") (pinfunction "2_2") (pintype "passive"))
      (node (ref "R83") (pin "2") (pinfunction "2_2") (pintype "passive"))
      (node (ref "R94") (pin "2") (pinfunction "2_2") (pintype "passive"))
      (node (ref "R96") (pin "2") (pinfunction "2_2") (pintype "passive"))
    )
    (net (code "3") (name "+5V") (class "Default")
      (node (ref "C12") (pin "2") (pinfunction "2_2") (pintype "passive"))
      (node (ref "C13") (pin "2") (pinfunction "2_2") (pintype "passive"))
      (node (ref "C14") (pin "2") (pinfunction "2_2") (pintype "passive"))
      (node (ref "C15") (pin "2") (pinfunction "2_2") (pintype "passive"))
      (node (ref "C36") (pin "2") (pinfunction "2_2") (pintype "passive"))
      (node (ref "C40") (pin "2") (pinfunction "2_2") (pintype "passive"))
      (node (ref "C5") (pin "1") (pinfunction "1_1") (pintype "passive"))
      (node (ref "C7") (pin "2") (pinfunction "2_2") (pintype "passive"))
      (node (ref "C8") (pin "2") (pinfunction "2_2") (pintype "passive"))
      (node (ref "GPS1") (pin "1") (pinfunction "VIN_1") (pintype "passive"))
      (node (ref "P2") (pin "1") (pinfunction "1_1") (pintype "passive"))
      (node (ref "P9") (pin "2") (pinfunction "2_2") (pintype "passive"))
      (node (ref "Q1") (pin "3") (pinfunction "S_3") (pintype "passive"))
      (node (ref "R121") (pin "2") (pinfunction "2_2") (pintype "passive"))
      (node (ref "R15") (pin "1") (pinfunction "TOP_1") (pintype "passive"))
      (node (ref "R50") (pin "2") (pinfunction "2_2") (pintype "passive"))
      (node (ref "R79") (pin "1") (pinfunction "1_1") (pintype "passive"))
      (node (ref "R80") (pin "1") (pinfunction "1_1") (pintype "passive"))
      (node (ref "R82") (pin "2") (pinfunction "2_2") (pintype "passive"))
      (node (ref "R84") (pin "2") (pinfunction "2_2") (pintype "passive"))
      (node (ref "R95") (pin "2") (pinfunction "2_2") (pintype "passive"))
      (node (ref "R97") (pin "2") (pinfunction "2_2") (pintype "passive"))
      (node (ref "U1") (pin "3") (pinfunction "OUT+_3") (pintype "passive"))
      (node (ref "U14") (pin "8") (pinfunction "VCC_8") (pintype "power_in"))
      (node (ref "U4") (pin "11") (pinfunction "VDD_11") (pintype "power_in"))
      (node (ref "U4") (pin "21") (pinfunction "VDD_21") (pintype "power_in"))
      (node (ref "U4") (pin "32") (pinfunction "VDD_32") (pintype "power_in"))
      (node (ref "U4") (pin "40") (pinfunction "AVDD_40") (pintype "power_in"))
    )
    (net (code "4") (name "+12V") (class "Default")
      (node (ref "C16") (pin "1") (pinfunction "1_1") (pintype "passive"))
      (node (ref "C18") (pin "2") (pinfunction "2_2") (pintype "passive"))
      (node (ref "C25") (pin "2") (pinfunction "2_2") (pintype "passive"))
      (node (ref "C31") (pin "2") (pinfunction "2_2") (pintype "passive"))
      (node (ref "C4") (pin "1") (pinfunction "1_1") (pintype "passive"))
      (node (ref "C43") (pin "2") (pinfunction "2_2") (pintype "passive"))
      (node (ref "C57") (pin "2") (pinfunction "2_2") (pintype "passive"))
      (node (ref "C6") (pin "2") (pinfunction "2_2") (pintype "passive"))
      (node (ref "D2") (pin "2") (pinfunction "K_2") (pintype "passive"))
      (node (ref "D4") (pin "2") (pinfunction "K_2") (pintype "passive"))
      (node (ref "P7") (pin "1") (pinfunction "1_1") (pintype "passive"))
      (node (ref "R114") (pin "1") (pinfunction "1_1") (pintype "passive"))
      (node (ref "R46") (pin "1") (pinfunction "1_1") (pintype "passive"))
      (node (ref "R76") (pin "1") (pinfunction "1_1") (pintype "passive"))
      (node (ref "U1") (pin "1") (pinfunction "IN+_1") (pintype "passive"))
      (node (ref "U10") (pin "4") (pinfunction "V+_4") (pintype "power_in"))
      (node (ref "U13") (pin "4") (pinfunction "V+_4") (pintype "power_in"))
      (node (ref "U17") (pin "4") (pinfunction "V+_4") (pintype "power_in"))
      (node (ref "U2") (pin "8") (pinfunction "VDD_8") (pintype "power_in"))
      (node (ref "U3") (pin "8") (pinfunction "VDD_8") (pintype "power_in"))
      (node (ref "U5") (pin "2") (pinfunction "IN_2") (pintype "power_in"))
      (node (ref "U7") (pin "8") (pinfunction "V+_8") (pintype "power_in"))
    )
    (net (code "5") (name "-2.5V") (class "Default")
      (node (ref "C33") (pin "2") (pinfunction "2_2") (pintype "passive"))
      (node (ref "C45") (pin "2") (pinfunction "2_2") (pintype "passive"))
      (node (ref "C59") (pin "2") (pinfunction "2_2") (pintype "passive"))
      (node (ref "P4") (pin "3") (pinfunction "3_3") (pintype "passive"))
      (node (ref "U11") (pin "27") (pinfunction "VSS_27") (pintype "power_in"))
      (node (ref "U15") (pin "27") (pinfunction "VSS_27") (pintype "power_in"))
      (node (ref "U8") (pin "27") (pinfunction "VSS_27") (pintype "power_in"))
    )
    (net (code "6") (name "-12V") (class "Default")
      (node (ref "C1") (pin "2") (pinfunction "2_2") (pintype "passive"))
      (node (ref "C19") (pin "2") (pinfunction "2_2") (pintype "passive"))
      (node (ref "C2") (pin "1") (pinfunction "1_1") (pintype "passive"))
      (node (ref "C21") (pin "2") (pinfunction "2_2") (pintype "passive"))
      (node (ref "C24") (pin "2") (pinfunction "2_2") (pintype "passive"))
      (node (ref "C28") (pin "2") (pinfunction "2_2") (pintype "passive"))
      (node (ref "C39") (pin "2") (pinfunction "2_2") (pintype "passive"))
      (node (ref "C54") (pin "2") (pinfunction "2_2") (pintype "passive"))
      (node (ref "P7") (pin "3") (pinfunction "3_3") (pintype "passive"))
      (node (ref "R113") (pin "1") (pinfunction "1_1") (pintype "passive"))
      (node (ref "R45") (pin "1") (pinfunction "1_1") (pintype "passive"))
      (node (ref "R75") (pin "1") (pinfunction "1_1") (pintype "passive"))
      (node (ref "U10") (pin "11") (pinfunction "V-_11") (pintype "power_in"))
      (node (ref "U13") (pin "11") (pinfunction "V-_11") (pintype "power_in"))
      (node (ref "U17") (pin "11") (pinfunction "V-_11") (pintype "power_in"))
      (node (ref "U2") (pin "5") (pinfunction "VOUT_5") (pintype "power_in"))
      (node (ref "U3") (pin "5") (pinfunction "VOUT_5") (pintype "power_in"))
      (node (ref "U6") (pin "3") (pinfunction "IN_3") (pintype "power_in"))
      (node (ref "U7") (pin "4") (pinfunction "V-_4") (pintype "power_in"))
    )
    (net (code "7") (name "5V_RPi") (class "Default")
      (node (ref "C50") (pin "2") (pinfunction "2_2") (pintype "passive"))
      (node (ref "C51") (pin "2") (pinfunction "2_2") (pintype "passive"))
      (node (ref "P12") (pin "2") (pinfunction "2_2") (pintype "passive"))
      (node (ref "P12") (pin "4") (pinfunction "4_4") (pintype "passive"))
      (node (ref "P8") (pin "2") (pinfunction "2_2") (pintype "passive"))
    )
    (net (code "8") (name "A0") (class "Default")
      (node (ref "R14") (pin "2") (pinfunction "2_2") (pintype "passive"))
      (node (ref "R5") (pin "1") (pinfunction "1_1") (pintype "passive"))
      (node (ref "U11") (pin "17") (pinfunction "A0_17") (pintype "input"))
      (node (ref "U15") (pin "17") (pinfunction "A0_17") (pintype "input"))
      (node (ref "U8") (pin "17") (pinfunction "A0_17") (pintype "input"))
    )
    (net (code "9") (name "A1") (class "Default")
      (node (ref "R13") (pin "2") (pinfunction "2_2") (pintype "passive"))
      (node (ref "R4") (pin "1") (pinfunction "1_1") (pintype "passive"))
      (node (ref "U11") (pin "16") (pinfunction "A1_16") (pintype "input"))
      (node (ref "U15") (pin "16") (pinfunction "A1_16") (pintype "input"))
      (node (ref "U8") (pin "16") (pinfunction "A1_16") (pintype "input"))
    )
    (net (code "10") (name "A2") (class "Default")
      (node (ref "R12") (pin "2") (pinfunction "2_2") (pintype "passive"))
      (node (ref "R3") (pin "1") (pinfunction "1_1") (pintype "passive"))
      (node (ref "U11") (pin "15") (pinfunction "A2_15") (pintype "input"))
      (node (ref "U15") (pin "15") (pinfunction "A2_15") (pintype "input"))
      (node (ref "U8") (pin "15") (pinfunction "A2_15") (pintype "input"))
    )
    (net (code "11") (name "A3") (class "Default")
      (node (ref "R11") (pin "2") (pinfunction "2_2") (pintype "passive"))
      (node (ref "R2") (pin "1") (pinfunction "1_1") (pintype "passive"))
      (node (ref "U11") (pin "14") (pinfunction "A3_14") (pintype "input"))
      (node (ref "U15") (pin "14") (pinfunction "A3_14") (pintype "input"))
      (node (ref "U8") (pin "14") (pinfunction "A3_14") (pintype "input"))
    )
    (net (code "12") (name "C1+") (class "Default")
      (node (ref "P6") (pin "1") (pinfunction "1_1") (pintype "passive"))
      (node (ref "R33") (pin "1") (pinfunction "1_1") (pintype "passive"))
      (node (ref "U9") (pin "3") (pinfunction "3_3") (pintype "input"))
    )
    (net (code "13") (name "C1-") (class "Default")
      (node (ref "P6") (pin "2") (pinfunction "2_2") (pintype "passive"))
      (node (ref "R23") (pin "2") (pinfunction "2_2") (pintype "passive"))
      (node (ref "U9") (pin "2") (pinfunction "2_2") (pintype "input"))
    )
    (net (code "14") (name "C2+") (class "Default")
      (node (ref "P6") (pin "3") (pinfunction "3_3") (pintype "passive"))
      (node (ref "R65") (pin "1") (pinfunction "1_1") (pintype "passive"))
      (node (ref "U12") (pin "3") (pinfunction "3_3") (pintype "input"))
    )
    (net (code "15") (name "C2-") (class "Default")
      (node (ref "P6") (pin "4") (pinfunction "4_4") (pintype "passive"))
      (node (ref "R56") (pin "2") (pinfunction "2_2") (pintype "passive"))
      (node (ref "U12") (pin "2") (pinfunction "2_2") (pintype "input"))
    )
    (net (code "16") (name "C3+") (class "Default")
      (node (ref "P6") (pin "5") (pinfunction "5_5") (pintype "passive"))
      (node (ref "R103") (pin "1") (pinfunction "1_1") (pintype "passive"))
      (node (ref "U16") (pin "3") (pinfunction "3_3") (pintype "input"))
    )
    (net (code "17") (name "C3-") (class "Default")
      (node (ref "P6") (pin "6") (pinfunction "6_6") (pintype "passive"))
      (node (ref "R90") (pin "2") (pinfunction "2_2") (pintype "passive"))
      (node (ref "U16") (pin "2") (pinfunction "2_2") (pintype "input"))
    )
    (net (code "18") (name "CS_3.3V") (class "Default")
      (node (ref "P12") (pin "24") (pinfunction "24_24") (pintype "passive"))
      (node (ref "Q3") (pin "2") (pinfunction "S_2") (pintype "passive"))
      (node (ref "R81") (pin "1") (pinfunction "1_1") (pintype "passive"))
    )
    (net (code "19") (name "CS_5V") (class "Default")
      (node (ref "Q3") (pin "3") (pinfunction "D_3") (pintype "passive"))
      (node (ref "R82") (pin "1") (pinfunction "1_1") (pintype "passive"))
      (node (ref "U4") (pin "4") (pinfunction "AN2/~{SS1}/LVDIN/CN4/RB2_4") (pintype "bidirectional"))
    )
    (net (code "20") (name "Cristal1") (class "Default")
      (node (ref "C3") (pin "1") (pinfunction "1_1") (pintype "passive"))
      (node (ref "U4") (pin "13") (pinfunction "OSC1/CLKI_13") (pintype "input"))
      (node (ref "Y1") (pin "2") (pinfunction "OSC2_2") (pintype "passive"))
    )
    (net (code "21") (name "Cristal2") (class "Default")
      (node (ref "C11") (pin "1") (pinfunction "1_1") (pintype "passive"))
      (node (ref "U4") (pin "14") (pinfunction "OSC2/CLKO/RC15_14") (pintype "bidirectional"))
      (node (ref "Y1") (pin "1") (pinfunction "OSC1_1") (pintype "passive"))
    )
    (net (code "22") (name "EN_GPS") (class "Default")
      (node (ref "GPS1") (pin "7") (pinfunction "EN_7") (pintype "passive"))
      (node (ref "U4") (pin "19") (pinfunction "RD3_19") (pintype "bidirectional"))
    )
    (net (code "23") (name "GND") (class "Default")
      (node (ref "BT1") (pin "1") (pinfunction "-_1") (pintype "passive"))
      (node (ref "C1") (pin "1") (pinfunction "1_1") (pintype "passive"))
      (node (ref "C11") (pin "2") (pinfunction "2_2") (pintype "passive"))
      (node (ref "C12") (pin "1") (pinfunction "1_1") (pintype "passive"))
      (node (ref "C13") (pin "1") (pinfunction "1_1") (pintype "passive"))
      (node (ref "C14") (pin "1") (pinfunction "1_1") (pintype "passive"))
      (node (ref "C15") (pin "1") (pinfunction "1_1") (pintype "passive"))
      (node (ref "C16") (pin "2") (pinfunction "2_2") (pintype "passive"))
      (node (ref "C17") (pin "2") (pinfunction "2_2") (pintype "passive"))
      (node (ref "C18") (pin "1") (pinfunction "1_1") (pintype "passive"))
      (node (ref "C19") (pin "1") (pinfunction "1_1") (pintype "passive"))
      (node (ref "C2") (pin "2") (pinfunction "2_2") (pintype "passive"))
      (node (ref "C20") (pin "1") (pinfunction "1_1") (pintype "passive"))
      (node (ref "C21") (pin "1") (pinfunction "1_1") (pintype "passive"))
      (node (ref "C22") (pin "1") (pinfunction "1_1") (pintype "passive"))
      (node (ref "C23") (pin "1") (pinfunction "1_1") (pintype "passive"))
      (node (ref "C24") (pin "1") (pinfunction "1_1") (pintype "passive"))
      (node (ref "C25") (pin "1") (pinfunction "1_1") (pintype "passive"))
      (node (ref "C28") (pin "1") (pinfunction "1_1") (pintype "passive"))
      (node (ref "C29") (pin "2") (pinfunction "2_2") (pintype "passive"))
      (node (ref "C3") (pin "2") (pinfunction "2_2") (pintype "passive"))
      (node (ref "C30") (pin "2") (pinfunction "2_2") (pintype "passive"))
      (node (ref "C31") (pin "1") (pinfunction "1_1") (pintype "passive"))
      (node (ref "C32") (pin "1") (pinfunction "1_1") (pintype "passive"))
      (node (ref "C33") (pin "1") (pinfunction "1_1") (pintype "passive"))
      (node (ref "C34") (pin "1") (pinfunction "1_1") (pintype "passive"))
      (node (ref "C35") (pin "1") (pinfunction "1_1") (pintype "passive"))
      (node (ref "C36") (pin "1") (pinfunction "1_1") (pintype "passive"))
      (node (ref "C39") (pin "1") (pinfunction "1_1") (pintype "passive"))
      (node (ref "C4") (pin "2") (pinfunction "2_2") (pintype "passive"))
      (node (ref "C40") (pin "1") (pinfunction "1_1") (pintype "passive"))
      (node (ref "C41") (pin "2") (pinfunction "2_2") (pintype "passive"))
      (node (ref "C42") (pin "2") (pinfunction "2_2") (pintype "passive"))
      (node (ref "C43") (pin "1") (pinfunction "1_1") (pintype "passive"))
      (node (ref "C44") (pin "1") (pinfunction "1_1") (pintype "passive"))
      (node (ref "C45") (pin "1") (pinfunction "1_1") (pintype "passive"))
      (node (ref "C46") (pin "1") (pinfunction "1_1") (pintype "passive"))
      (node (ref "C47") (pin "1") (pinfunction "1_1") (pintype "passive"))
      (node (ref "C48") (pin "1") (pinfunction "1_1") (pintype "passive"))
      (node (ref "C49") (pin "1") (pinfunction "1_1") (pintype "passive"))
      (node (ref "C5") (pin "2") (pinfunction "2_2") (pintype "passive"))
      (node (ref "C50") (pin "1") (pinfunction "1_1") (pintype "passive"))
      (node (ref "C51") (pin "1") (pinfunction "1_1") (pintype "passive"))
      (node (ref "C54") (pin "1") (pinfunction "1_1") (pintype "passive"))
      (node (ref "C55") (pin "2") (pinfunction "2_2") (pintype "passive"))
      (node (ref "C56") (pin "2") (pinfunction "2_2") (pintype "passive"))
      (node (ref "C57") (pin "1") (pinfunction "1_1") (pintype "passive"))
      (node (ref "C58") (pin "1") (pinfunction "1_1") (pintype "passive"))
      (node (ref "C59") (pin "1") (pinfunction "1_1") (pintype "passive"))
      (node (ref "C6") (pin "1") (pinfunction "1_1") (pintype "passive"))
      (node (ref "C60") (pin "1") (pinfunction "1_1") (pintype "passive"))
      (node (ref "C61") (pin "1") (pinfunction "1_1") (pintype "passive"))
      (node (ref "C7") (pin "1") (pinfunction "1_1") (pintype "passive"))
      (node (ref "C8") (pin "1") (pinfunction "1_1") (pintype "passive"))
      (node (ref "D1") (pin "1") (pinfunction "A_1") (pintype "passive"))
      (node (ref "D3") (pin "1") (pinfunction "A_1") (pintype "passive"))
      (node (ref "GPS1") (pin "2") (pinfunction "GND_2") (pintype "passive"))
      (node (ref "P11") (pin "2") (pinfunction "2_2") (pintype "passive"))
      (node (ref "P12") (pin "14") (pinfunction "14_14") (pintype "passive"))
      (node (ref "P12") (pin "20") (pinfunction "20_20") (pintype "passive"))
      (node (ref "P12") (pin "25") (pinfunction "25_25") (pintype "passive"))
      (node (ref "P12") (pin "30") (pinfunction "30_30") (pintype "passive"))
      (node (ref "P12") (pin "34") (pinfunction "34_34") (pintype "passive"))
      (node (ref "P12") (pin "39") (pinfunction "39_39") (pintype "passive"))
      (node (ref "P12") (pin "6") (pinfunction "6_6") (pintype "passive"))
      (node (ref "P12") (pin "9") (pinfunction "9_9") (pintype "passive"))
      (node (ref "P13") (pin "2") (pinfunction "2_2") (pintype "passive"))
      (node (ref "P13") (pin "4") (pinfunction "4_4") (pintype "passive"))
      (node (ref "P2") (pin "2") (pinfunction "2_2") (pintype "passive"))
      (node (ref "P5") (pin "2") (pinfunction "2_2") (pintype "passive"))
      (node (ref "P5") (pin "4") (pinfunction "4_4") (pintype "passive"))
      (node (ref "P7") (pin "2") (pinfunction "2_2") (pintype "passive"))
      (node (ref "P7") (pin "4") (pinfunction "4_4") (pintype "passive"))
      (node (ref "P9") (pin "3") (pinfunction "3_3") (pintype "passive"))
      (node (ref "R103") (pin "2") (pinfunction "2_2") (pintype "passive"))
      (node (ref "R11") (pin "1") (pinfunction "1_1") (pintype "passive"))
      (node (ref "R116") (pin "2") (pinfunction "2_2") (pintype "passive"))
      (node (ref "R119") (pin "1") (pinfunction "1_1") (pintype "passive"))
      (node (ref "R12") (pin "1") (pinfunction "1_1") (pintype "passive"))
      (node (ref "R13") (pin "1") (pinfunction "1_1") (pintype "passive"))
      (node (ref "R14") (pin "1") (pinfunction "1_1") (pintype "passive"))
      (node (ref "R15") (pin "2") (pinfunction "BOT_2") (pintype "passive"))
      (node (ref "R18") (pin "1") (pinfunction "1_1") (pintype "passive"))
      (node (ref "R19") (pin "1") (pinfunction "1_1") (pintype "passive"))
      (node (ref "R23") (pin "1") (pinfunction "1_1") (pintype "passive"))
      (node (ref "R26") (pin "1") (pinfunction "1_1") (pintype "passive"))
      (node (ref "R33") (pin "2") (pinfunction "2_2") (pintype "passive"))
      (node (ref "R48") (pin "2") (pinfunction "2_2") (pintype "passive"))
      (node (ref "R56") (pin "1") (pinfunction "1_1") (pintype "passive"))
      (node (ref "R65") (pin "2") (pinfunction "2_2") (pintype "passive"))
      (node (ref "R78") (pin "2") (pinfunction "2_2") (pintype "passive"))
      (node (ref "R8") (pin "3") (pinfunction "TAP_3") (pintype "passive"))
      (node (ref "R9") (pin "3") (pinfunction "TAP_3") (pintype "passive"))
      (node (ref "R90") (pin "1") (pinfunction "1_1") (pintype "passive"))
      (node (ref "U1") (pin "2") (pinfunction "IN-_2") (pintype "passive"))
      (node (ref "U1") (pin "4") (pinfunction "OUT-_4") (pintype "passive"))
      (node (ref "U11") (pin "12") (pinfunction "GND_12") (pintype "power_in"))
      (node (ref "U12") (pin "5") (pinfunction "5_5") (pintype "power_in"))
      (node (ref "U14") (pin "4") (pinfunction "GND_4") (pintype "power_in"))
      (node (ref "U15") (pin "12") (pinfunction "GND_12") (pintype "power_in"))
      (node (ref "U16") (pin "5") (pinfunction "5_5") (pintype "power_in"))
      (node (ref "U2") (pin "3") (pinfunction "GND_3") (pintype "power_in"))
      (node (ref "U3") (pin "3") (pinfunction "GND_3") (pintype "power_in"))
      (node (ref "U4") (pin "12") (pinfunction "VSS_12") (pintype "power_in"))
      (node (ref "U4") (pin "20") (pinfunction "VSS_20") (pintype "power_in"))
      (node (ref "U4") (pin "31") (pinfunction "VSS_31") (pintype "power_in"))
      (node (ref "U4") (pin "39") (pinfunction "AVSS_39") (pintype "power_in"))
      (node (ref "U8") (pin "12") (pinfunction "GND_12") (pintype "power_in"))
      (node (ref "U9") (pin "5") (pinfunction "5_5") (pintype "power_in"))
    )
    (net (code "24") (name "INT_FROM_PIC") (class "Default")
      (node (ref "P12") (pin "11") (pinfunction "11_11") (pintype "passive"))
      (node (ref "R16") (pin "1") (pinfunction "1_1") (pintype "passive"))
      (node (ref "R18") (pin "2") (pinfunction "2_2") (pintype "passive"))
    )
    (net (code "25") (name "INreloj") (class "Default")
      (node (ref "U14") (pin "7") (pinfunction "OUT_7") (pintype "output"))
      (node (ref "U4") (pin "18") (pinfunction "IC2/INT2/RD9_18") (pintype "bidirectional"))
    )
    (net (code "26") (name "LED_PIC_1") (class "Default")
      (node (ref "P5") (pin "1") (pinfunction "1_1") (pintype "passive"))
      (node (ref "R1") (pin "1") (pinfunction "1_1") (pintype "passive"))
    )
    (net (code "27") (name "LED_PIC_2") (class "Default")
      (node (ref "P5") (pin "3") (pinfunction "3_3") (pintype "passive"))
      (node (ref "R10") (pin "1") (pinfunction "1_1") (pintype "passive"))
    )
    (net (code "28") (name "LED_RPi_1") (class "Default")
      (node (ref "P13") (pin "1") (pinfunction "1_1") (pintype "passive"))
      (node (ref "R117") (pin "1") (pinfunction "1_1") (pintype "passive"))
    )
    (net (code "29") (name "LED_RPi_2") (class "Default")
      (node (ref "P13") (pin "3") (pinfunction "3_3") (pintype "passive"))
      (node (ref "R118") (pin "1") (pinfunction "1_1") (pintype "passive"))
    )
    (net (code "30") (name "MCLR") (class "Default")
      (node (ref "P10") (pin "2") (pinfunction "2_2") (pintype "passive"))
      (node (ref "P9") (pin "1") (pinfunction "1_1") (pintype "passive"))
      (node (ref "U4") (pin "1") (pinfunction "~{MCLR}_1") (pintype "input"))
    )
    (net (code "31") (name "MISO_3.3V") (class "Default")
      (node (ref "P12") (pin "21") (pinfunction "21_21") (pintype "passive"))
      (node (ref "R17") (pin "1") (pinfunction "1_1") (pintype "passive"))
      (node (ref "R19") (pin "2") (pinfunction "2_2") (pintype "passive"))
    )
    (net (code "32") (name "MOSI_3.3V") (class "Default")
      (node (ref "P12") (pin "19") (pinfunction "19_19") (pintype "passive"))
      (node (ref "Q4") (pin "2") (pinfunction "S_2") (pintype "passive"))
      (node (ref "R83") (pin "1") (pinfunction "1_1") (pintype "passive"))
    )
    (net (code "33") (name "MOSI_5V") (class "Default")
      (node (ref "Q4") (pin "3") (pinfunction "D_3") (pintype "passive"))
      (node (ref "R84") (pin "1") (pinfunction "1_1") (pintype "passive"))
      (node (ref "U4") (pin "26") (pinfunction "U1RX/SDI1/SDA/RF2_26") (pintype "bidirectional"))
    )
    (net (code "34") (name "Net-(BT1-+)") (class "Default")
      (node (ref "BT1") (pin "0") (pinfunction "+_0") (pintype "passive"))
      (node (ref "U14") (pin "3") (pinfunction "Vbat_3") (pintype "power_in"))
    )
    (net (code "35") (name "Net-(C26-Pad2)") (class "Default")
      (node (ref "C26") (pin "2") (pinfunction "2_2") (pintype "passive"))
      (node (ref "R31") (pin "2") (pinfunction "2_2") (pintype "passive"))
      (node (ref "R32") (pin "1") (pinfunction "1_1") (pintype "passive"))
    )
    (net (code "36") (name "Net-(C27-Pad2)") (class "Default")
      (node (ref "C27") (pin "2") (pinfunction "2_2") (pintype "passive"))
      (node (ref "R35") (pin "2") (pinfunction "2_2") (pintype "passive"))
      (node (ref "R36") (pin "1") (pinfunction "1_1") (pintype "passive"))
    )
    (net (code "37") (name "Net-(C34-Pad2)") (class "Default")
      (node (ref "C34") (pin "2") (pinfunction "2_2") (pintype "passive"))
      (node (ref "R45") (pin "2") (pinfunction "2_2") (pintype "passive"))
      (node (ref "U9") (pin "4") (pinfunction "4_4") (pintype "power_in"))
    )
    (net (code "38") (name "Net-(C35-Pad2)") (class "Default")
      (node (ref "C35") (pin "2") (pinfunction "2_2") (pintype "passive"))
      (node (ref "R46") (pin "2") (pinfunction "2_2") (pintype "passive"))
      (node (ref "U9") (pin "7") (pinfunction "7_7") (pintype "power_in"))
    )
    (net (code "39") (name "Net-(C37-Pad2)") (class "Default")
      (node (ref "C37") (pin "2") (pinfunction "2_2") (pintype "passive"))
      (node (ref "R62") (pin "2") (pinfunction "2_2") (pintype "passive"))
      (node (ref "R63") (pin "1") (pinfunction "1_1") (pintype "passive"))
    )
    (net (code "40") (name "Net-(C38-Pad2)") (class "Default")
      (node (ref "C38") (pin "2") (pinfunction "2_2") (pintype "passive"))
      (node (ref "R66") (pin "2") (pinfunction "2_2") (pintype "passive"))
      (node (ref "R67") (pin "1") (pinfunction "1_1") (pintype "passive"))
    )
    (net (code "41") (name "Net-(C46-Pad2)") (class "Default")
      (node (ref "C46") (pin "2") (pinfunction "2_2") (pintype "passive"))
      (node (ref "R75") (pin "2") (pinfunction "2_2") (pintype "passive"))
      (node (ref "U12") (pin "4") (pinfunction "4_4") (pintype "power_in"))
    )
    (net (code "42") (name "Net-(C47-Pad2)") (class "Default")
      (node (ref "C47") (pin "2") (pinfunction "2_2") (pintype "passive"))
      (node (ref "R76") (pin "2") (pinfunction "2_2") (pintype "passive"))
      (node (ref "U12") (pin "7") (pinfunction "7_7") (pintype "power_in"))
    )
    (net (code "43") (name "Net-(C52-Pad2)") (class "Default")
      (node (ref "C52") (pin "2") (pinfunction "2_2") (pintype "passive"))
      (node (ref "R100") (pin "2") (pinfunction "2_2") (pintype "passive"))
      (node (ref "R101") (pin "1") (pinfunction "1_1") (pintype "passive"))
    )
    (net (code "44") (name "Net-(C53-Pad2)") (class "Default")
      (node (ref "C53") (pin "2") (pinfunction "2_2") (pintype "passive"))
      (node (ref "R104") (pin "2") (pinfunction "2_2") (pintype "passive"))
      (node (ref "R105") (pin "1") (pinfunction "1_1") (pintype "passive"))
    )
    (net (code "45") (name "Net-(C60-Pad2)") (class "Default")
      (node (ref "C60") (pin "2") (pinfunction "2_2") (pintype "passive"))
      (node (ref "R113") (pin "2") (pinfunction "2_2") (pintype "passive"))
      (node (ref "U16") (pin "4") (pinfunction "4_4") (pintype "power_in"))
    )
    (net (code "46") (name "Net-(C61-Pad2)") (class "Default")
      (node (ref "C61") (pin "2") (pinfunction "2_2") (pintype "passive"))
      (node (ref "R114") (pin "2") (pinfunction "2_2") (pintype "passive"))
      (node (ref "U16") (pin "7") (pinfunction "7_7") (pintype "power_in"))
    )
    (net (code "47") (name "Net-(D1-K)") (class "Default")
      (node (ref "D1") (pin "2") (pinfunction "K_2") (pintype "passive"))
      (node (ref "D2") (pin "1") (pinfunction "A_1") (pintype "passive"))
      (node (ref "P1") (pin "1") (pinfunction "1_1") (pintype "passive"))
    )
    (net (code "48") (name "Net-(D3-K)") (class "Default")
      (node (ref "D3") (pin "2") (pinfunction "K_2") (pintype "passive"))
      (node (ref "D4") (pin "1") (pinfunction "A_1") (pintype "passive"))
      (node (ref "P1") (pin "2") (pinfunction "2_2") (pintype "passive"))
    )
    (net (code "49") (name "Net-(P12-Pad32)") (class "Default")
      (node (ref "P12") (pin "32") (pinfunction "32_32") (pintype "passive"))
      (node (ref "R117") (pin "2") (pinfunction "2_2") (pintype "passive"))
    )
    (net (code "50") (name "Net-(P12-Pad36)") (class "Default")
      (node (ref "P12") (pin "36") (pinfunction "36_36") (pintype "passive"))
      (node (ref "R118") (pin "2") (pinfunction "2_2") (pintype "passive"))
    )
    (net (code "51") (name "Net-(Q1-D)") (class "Default")
      (node (ref "P8") (pin "1") (pinfunction "1_1") (pintype "passive"))
      (node (ref "Q1") (pin "1") (pinfunction "D_1") (pintype "passive"))
    )
    (net (code "52") (name "Net-(R8-TOP)") (class "Default")
      (node (ref "R6") (pin "1") (pinfunction "1_1") (pintype "passive"))
      (node (ref "R8") (pin "1") (pinfunction "TOP_1") (pintype "passive"))
      (node (ref "U5") (pin "1") (pinfunction "ADJ_1") (pintype "input"))
    )
    (net (code "53") (name "Net-(R9-TOP)") (class "Default")
      (node (ref "R7") (pin "1") (pinfunction "1_1") (pintype "passive"))
      (node (ref "R9") (pin "1") (pinfunction "TOP_1") (pintype "passive"))
      (node (ref "U6") (pin "1") (pinfunction "ADJ_1") (pintype "input"))
    )
    (net (code "54") (name "Net-(R15-TAP)") (class "Default")
      (node (ref "R15") (pin "3") (pinfunction "TAP_3") (pintype "passive"))
      (node (ref "U7") (pin "3") (pinfunction "IN+_3") (pintype "input"))
    )
    (net (code "55") (name "Net-(R31-Pad1)") (class "Default")
      (node (ref "R31") (pin "1") (pinfunction "1_1") (pintype "passive"))
      (node (ref "U9") (pin "6") (pinfunction "6_6") (pintype "output"))
    )
    (net (code "56") (name "Net-(R62-Pad1)") (class "Default")
      (node (ref "R62") (pin "1") (pinfunction "1_1") (pintype "passive"))
      (node (ref "U12") (pin "6") (pinfunction "6_6") (pintype "output"))
    )
    (net (code "57") (name "Net-(R100-Pad1)") (class "Default")
      (node (ref "R100") (pin "1") (pinfunction "1_1") (pintype "passive"))
      (node (ref "U16") (pin "6") (pinfunction "6_6") (pintype "output"))
    )
    (net (code "58") (name "Net-(U2-C+)") (class "Default")
      (node (ref "C9") (pin "1") (pinfunction "1_1") (pintype "passive"))
      (node (ref "U2") (pin "2") (pinfunction "C+_2") (pintype "passive"))
    )
    (net (code "59") (name "Net-(U2-C-)") (class "Default")
      (node (ref "C9") (pin "2") (pinfunction "2_2") (pintype "passive"))
      (node (ref "U2") (pin "4") (pinfunction "C-_4") (pintype "passive"))
    )
    (net (code "60") (name "Net-(U3-C+)") (class "Default")
      (node (ref "C10") (pin "1") (pinfunction "1_1") (pintype "passive"))
      (node (ref "U3") (pin "2") (pinfunction "C+_2") (pintype "passive"))
    )
    (net (code "61") (name "Net-(U3-C-)") (class "Default")
      (node (ref "C10") (pin "2") (pinfunction "2_2") (pintype "passive"))
      (node (ref "U3") (pin "4") (pinfunction "C-_4") (pintype "passive"))
    )
    (net (code "62") (name "Net-(U4-AN0{slash}VREF+{slash}CN2{slash}RB0)") (class "Default")
      (node (ref "R1") (pin "2") (pinfunction "2_2") (pintype "passive"))
      (node (ref "U4") (pin "2") (pinfunction "AN0/VREF+/CN2/RB0_2") (pintype "bidirectional"))
    )
    (net (code "63") (name "Net-(U4-AN3{slash}CN5{slash}RB3)") (class "Default")
      (node (ref "R5") (pin "2") (pinfunction "2_2") (pintype "passive"))
      (node (ref "U4") (pin "5") (pinfunction "AN3/CN5/RB3_5") (pintype "bidirectional"))
    )
    (net (code "64") (name "Net-(U4-AN4{slash}CN6{slash}RB4)") (class "Default")
      (node (ref "R4") (pin "2") (pinfunction "2_2") (pintype "passive"))
      (node (ref "U4") (pin "6") (pinfunction "AN4/CN6/RB4_6") (pintype "bidirectional"))
    )
    (net (code "65") (name "Net-(U4-AN5{slash}CN7{slash}RB5)") (class "Default")
      (node (ref "R3") (pin "2") (pinfunction "2_2") (pintype "passive"))
      (node (ref "U4") (pin "7") (pinfunction "AN5/CN7/RB5_7") (pintype "bidirectional"))
    )
    (net (code "66") (name "Net-(U4-EMUC2{slash}OC1{slash}RD0)") (class "Default")
      (node (ref "R10") (pin "2") (pinfunction "2_2") (pintype "passive"))
      (node (ref "U4") (pin "34") (pinfunction "EMUC2/OC1/RD0_34") (pintype "bidirectional"))
    )
    (net (code "67") (name "Net-(U4-EMUD3{slash}U1TX{slash}SDO1{slash}SCL{slash}RF3)") (class "Default")
      (node (ref "R17") (pin "2") (pinfunction "2_2") (pintype "passive"))
      (node (ref "U4") (pin "25") (pinfunction "EMUD3/U1TX/SDO1/SCL/RF3_25") (pintype "bidirectional"))
    )
    (net (code "68") (name "Net-(U4-RF1)") (class "Default")
      (node (ref "R16") (pin "2") (pinfunction "2_2") (pintype "passive"))
      (node (ref "U4") (pin "29") (pinfunction "RF1_29") (pintype "bidirectional"))
    )
    (net (code "69") (name "Net-(U5-OUT)") (class "Default")
      (node (ref "C17") (pin "1") (pinfunction "1_1") (pintype "passive"))
      (node (ref "C20") (pin "2") (pinfunction "2_2") (pintype "passive"))
      (node (ref "P3") (pin "2") (pinfunction "2_2") (pintype "passive"))
      (node (ref "R6") (pin "2") (pinfunction "2_2") (pintype "passive"))
      (node (ref "U5") (pin "3") (pinfunction "OUT_3") (pintype "power_in"))
    )
    (net (code "70") (name "Net-(U6-OUT)") (class "Default")
      (node (ref "C22") (pin "2") (pinfunction "2_2") (pintype "passive"))
      (node (ref "C23") (pin "2") (pinfunction "2_2") (pintype "passive"))
      (node (ref "P4") (pin "2") (pinfunction "2_2") (pintype "passive"))
      (node (ref "R7") (pin "2") (pinfunction "2_2") (pintype "passive"))
      (node (ref "U6") (pin "2") (pinfunction "OUT_2") (pintype "power_in"))
    )
    (net (code "71") (name "Net-(U8-S1)") (class "Default")
      (node (ref "R20") (pin "2") (pinfunction "2_2") (pintype "passive"))
      (node (ref "U8") (pin "19") (pinfunction "S1_19") (pintype "input"))
    )
    (net (code "72") (name "Net-(U8-S2)") (class "Default")
      (node (ref "R21") (pin "2") (pinfunction "2_2") (pintype "passive"))
      (node (ref "U8") (pin "20") (pinfunction "S2_20") (pintype "input"))
    )
    (net (code "73") (name "Net-(U8-S3)") (class "Default")
      (node (ref "R22") (pin "2") (pinfunction "2_2") (pintype "passive"))
      (node (ref "U8") (pin "21") (pinfunction "S3_21") (pintype "input"))
    )
    (net (code "74") (name "Net-(U8-S4)") (class "Default")
      (node (ref "R24") (pin "2") (pinfunction "2_2") (pintype "passive"))
      (node (ref "U8") (pin "22") (pinfunction "S4_22") (pintype "input"))
    )
    (net (code "75") (name "Net-(U8-S5)") (class "Default")
      (node (ref "R25") (pin "2") (pinfunction "2_2") (pintype "passive"))
      (node (ref "U8") (pin "23") (pinfunction "S5_23") (pintype "input"))
    )
    (net (code "76") (name "Net-(U8-S6)") (class "Default")
      (node (ref "R27") (pin "2") (pinfunction "2_2") (pintype "passive"))
      (node (ref "U8") (pin "24") (pinfunction "S6_24") (pintype "input"))
    )
    (net (code "77") (name "Net-(U8-S7)") (class "Default")
      (node (ref "R28") (pin "2") (pinfunction "2_2") (pintype "passive"))
      (node (ref "U8") (pin "25") (pinfunction "S7_25") (pintype "input"))
    )
    (net (code "78") (name "Net-(U8-S8)") (class "Default")
      (node (ref "R29") (pin "2") (pinfunction "2_2") (pintype "passive"))
      (node (ref "U8") (pin "26") (pinfunction "S8_26") (pintype "input"))
    )
    (net (code "79") (name "Net-(U8-S9)") (class "Default")
      (node (ref "R30") (pin "2") (pinfunction "2_2") (pintype "passive"))
      (node (ref "U8") (pin "11") (pinfunction "S9_11") (pintype "input"))
    )
    (net (code "80") (name "Net-(U8-S10)") (class "Default")
      (node (ref "R34") (pin "2") (pinfunction "2_2") (pintype "passive"))
      (node (ref "U8") (pin "10") (pinfunction "S10_10") (pintype "input"))
    )
    (net (code "81") (name "Net-(U8-S11)") (class "Default")
      (node (ref "R37") (pin "2") (pinfunction "2_2") (pintype "passive"))
      (node (ref "U8") (pin "9") (pinfunction "S11_9") (pintype "input"))
    )
    (net (code "82") (name "Net-(U8-S12)") (class "Default")
      (node (ref "R39") (pin "2") (pinfunction "2_2") (pintype "passive"))
      (node (ref "U8") (pin "8") (pinfunction "S12_8") (pintype "input"))
    )
    (net (code "83") (name "Net-(U8-S13)") (class "Default")
      (node (ref "R40") (pin "2") (pinfunction "2_2") (pintype "passive"))
      (node (ref "U8") (pin "7") (pinfunction "S13_7") (pintype "input"))
    )
    (net (code "84") (name "Net-(U8-S14)") (class "Default")
      (node (ref "R41") (pin "2") (pinfunction "2_2") (pintype "passive"))
      (node (ref "U8") (pin "6") (pinfunction "S14_6") (pintype "input"))
    )
    (net (code "85") (name "Net-(U8-S15)") (class "Default")
      (node (ref "R42") (pin "2") (pinfunction "2_2") (pintype "passive"))
      (node (ref "U8") (pin "5") (pinfunction "S15_5") (pintype "input"))
    )
    (net (code "86") (name "Net-(U8-S16)") (class "Default")
      (node (ref "R43") (pin "2") (pinfunction "2_2") (pintype "passive"))
      (node (ref "U8") (pin "4") (pinfunction "S16_4") (pintype "input"))
    )
    (net (code "87") (name "Net-(U10A-IN+)") (class "Default")
      (node (ref "C29") (pin "1") (pinfunction "1_1") (pintype "passive"))
      (node (ref "R32") (pin "2") (pinfunction "2_2") (pintype "passive"))
      (node (ref "U10") (pin "3") (pinfunction "IN+_3") (pintype "input"))
    )
    (net (code "88") (name "Net-(U10A-IN-)") (class "Default")
      (node (ref "C26") (pin "1") (pinfunction "1_1") (pintype "passive"))
      (node (ref "R35") (pin "1") (pinfunction "1_1") (pintype "passive"))
      (node (ref "U10") (pin "1") (pinfunction "OUT_1") (pintype "output"))
      (node (ref "U10") (pin "2") (pinfunction "IN-_2") (pintype "input"))
    )
    (net (code "89") (name "Net-(U10B-IN+)") (class "Default")
      (node (ref "C30") (pin "1") (pinfunction "1_1") (pintype "passive"))
      (node (ref "R36") (pin "2") (pinfunction "2_2") (pintype "passive"))
      (node (ref "U10") (pin "5") (pinfunction "IN+_5") (pintype "input"))
    )
    (net (code "90") (name "Net-(U10B-IN-)") (class "Default")
      (node (ref "C27") (pin "1") (pinfunction "1_1") (pintype "passive"))
      (node (ref "R38") (pin "1") (pinfunction "1_1") (pintype "passive"))
      (node (ref "U10") (pin "6") (pinfunction "IN-_6") (pintype "input"))
      (node (ref "U10") (pin "7") (pinfunction "OUT_7") (pintype "output"))
    )
    (net (code "91") (name "Net-(U10C-IN+)") (class "Default")
      (node (ref "R38") (pin "2") (pinfunction "2_2") (pintype "passive"))
      (node (ref "R44") (pin "2") (pinfunction "2_2") (pintype "passive"))
      (node (ref "U10") (pin "10") (pinfunction "IN+_10") (pintype "input"))
    )
    (net (code "92") (name "Net-(U10C-IN-)") (class "Default")
      (node (ref "R47") (pin "1") (pinfunction "1_1") (pintype "passive"))
      (node (ref "R48") (pin "1") (pinfunction "1_1") (pintype "passive"))
      (node (ref "U10") (pin "9") (pinfunction "IN-_9") (pintype "input"))
    )
    (net (code "93") (name "Net-(U10C-OUT)") (class "Default")
      (node (ref "R47") (pin "2") (pinfunction "2_2") (pintype "passive"))
      (node (ref "U10") (pin "12") (pinfunction "IN+_12") (pintype "input"))
      (node (ref "U10") (pin "8") (pinfunction "OUT_8") (pintype "output"))
    )
    (net (code "94") (name "Net-(U11-S1)") (class "Default")
      (node (ref "R51") (pin "2") (pinfunction "2_2") (pintype "passive"))
      (node (ref "U11") (pin "19") (pinfunction "S1_19") (pintype "input"))
    )
    (net (code "95") (name "Net-(U11-S2)") (class "Default")
      (node (ref "R52") (pin "2") (pinfunction "2_2") (pintype "passive"))
      (node (ref "U11") (pin "20") (pinfunction "S2_20") (pintype "input"))
    )
    (net (code "96") (name "Net-(U11-S3)") (class "Default")
      (node (ref "R53") (pin "2") (pinfunction "2_2") (pintype "passive"))
      (node (ref "U11") (pin "21") (pinfunction "S3_21") (pintype "input"))
    )
    (net (code "97") (name "Net-(U11-S4)") (class "Default")
      (node (ref "R54") (pin "2") (pinfunction "2_2") (pintype "passive"))
      (node (ref "U11") (pin "22") (pinfunction "S4_22") (pintype "input"))
    )
    (net (code "98") (name "Net-(U11-S5)") (class "Default")
      (node (ref "R55") (pin "2") (pinfunction "2_2") (pintype "passive"))
      (node (ref "U11") (pin "23") (pinfunction "S5_23") (pintype "input"))
    )
    (net (code "99") (name "Net-(U11-S6)") (class "Default")
      (node (ref "R57") (pin "2") (pinfunction "2_2") (pintype "passive"))
      (node (ref "U11") (pin "24") (pinfunction "S6_24") (pintype "input"))
    )
    (net (code "100") (name "Net-(U11-S7)") (class "Default")
      (node (ref "R58") (pin "2") (pinfunction "2_2") (pintype "passive"))
      (node (ref "U11") (pin "25") (pinfunction "S7_25") (pintype "input"))
    )
    (net (code "101") (name "Net-(U11-S8)") (class "Default")
      (node (ref "R59") (pin "2") (pinfunction "2_2") (pintype "passive"))
      (node (ref "U11") (pin "26") (pinfunction "S8_26") (pintype "input"))
    )
    (net (code "102") (name "Net-(U11-S9)") (class "Default")
      (node (ref "R60") (pin "2") (pinfunction "2_2") (pintype "passive"))
      (node (ref "U11") (pin "11") (pinfunction "S9_11") (pintype "input"))
    )
    (net (code "103") (name "Net-(U11-S10)") (class "Default")
      (node (ref "R61") (pin "2") (pinfunction "2_2") (pintype "passive"))
      (node (ref "U11") (pin "10") (pinfunction "S10_10") (pintype "input"))
    )
    (net (code "104") (name "Net-(U11-S11)") (class "Default")
      (node (ref "R64") (pin "2") (pinfunction "2_2") (pintype "passive"))
      (node (ref "U11") (pin "9") (pinfunction "S11_9") (pintype "input"))
    )
    (net (code "105") (name "Net-(U11-S12)") (class "Default")
      (node (ref "R68") (pin "2") (pinfunction "2_2") (pintype "passive"))
      (node (ref "U11") (pin "8") (pinfunction "S12_8") (pintype "input"))
    )
    (net (code "106") (name "Net-(U11-S13)") (class "Default")
      (node (ref "R70") (pin "2") (pinfunction "2_2") (pintype "passive"))
      (node (ref "U11") (pin "7") (pinfunction "S13_7") (pintype "input"))
    )
    (net (code "107") (name "Net-(U11-S14)") (class "Default")
      (node (ref "R71") (pin "2") (pinfunction "2_2") (pintype "passive"))
      (node (ref "U11") (pin "6") (pinfunction "S14_6") (pintype "input"))
    )
    (net (code "108") (name "Net-(U11-S15)") (class "Default")
      (node (ref "R72") (pin "2") (pinfunction "2_2") (pintype "passive"))
      (node (ref "U11") (pin "5") (pinfunction "S15_5") (pintype "input"))
    )
    (net (code "109") (name "Net-(U11-S16)") (class "Default")
      (node (ref "R73") (pin "2") (pinfunction "2_2") (pintype "passive"))
      (node (ref "U11") (pin "4") (pinfunction "S16_4") (pintype "input"))
    )
    (net (code "110") (name "Net-(U13A-IN+)") (class "Default")
      (node (ref "C41") (pin "1") (pinfunction "1_1") (pintype "passive"))
      (node (ref "R63") (pin "2") (pinfunction "2_2") (pintype "passive"))
      (node (ref "U13") (pin "3") (pinfunction "IN+_3") (pintype "input"))
    )
    (net (code "111") (name "Net-(U13A-IN-)") (class "Default")
      (node (ref "C37") (pin "1") (pinfunction "1_1") (pintype "passive"))
      (node (ref "R66") (pin "1") (pinfunction "1_1") (pintype "passive"))
      (node (ref "U13") (pin "1") (pinfunction "OUT_1") (pintype "output"))
      (node (ref "U13") (pin "2") (pinfunction "IN-_2") (pintype "input"))
    )
    (net (code "112") (name "Net-(U13B-IN+)") (class "Default")
      (node (ref "C42") (pin "1") (pinfunction "1_1") (pintype "passive"))
      (node (ref "R67") (pin "2") (pinfunction "2_2") (pintype "passive"))
      (node (ref "U13") (pin "5") (pinfunction "IN+_5") (pintype "input"))
    )
    (net (code "113") (name "Net-(U13B-IN-)") (class "Default")
      (node (ref "C38") (pin "1") (pinfunction "1_1") (pintype "passive"))
      (node (ref "R69") (pin "1") (pinfunction "1_1") (pintype "passive"))
      (node (ref "U13") (pin "6") (pinfunction "IN-_6") (pintype "input"))
      (node (ref "U13") (pin "7") (pinfunction "OUT_7") (pintype "output"))
    )
    (net (code "114") (name "Net-(U13C-IN+)") (class "Default")
      (node (ref "R69") (pin "2") (pinfunction "2_2") (pintype "passive"))
      (node (ref "R74") (pin "2") (pinfunction "2_2") (pintype "passive"))
      (node (ref "U13") (pin "10") (pinfunction "IN+_10") (pintype "input"))
    )
    (net (code "115") (name "Net-(U13C-IN-)") (class "Default")
      (node (ref "R77") (pin "1") (pinfunction "1_1") (pintype "passive"))
      (node (ref "R78") (pin "1") (pinfunction "1_1") (pintype "passive"))
      (node (ref "U13") (pin "9") (pinfunction "IN-_9") (pintype "input"))
    )
    (net (code "116") (name "Net-(U13C-OUT)") (class "Default")
      (node (ref "R77") (pin "2") (pinfunction "2_2") (pintype "passive"))
      (node (ref "U13") (pin "12") (pinfunction "IN+_12") (pintype "input"))
      (node (ref "U13") (pin "8") (pinfunction "OUT_8") (pintype "output"))
    )
    (net (code "117") (name "Net-(U14-X1)") (class "Default")
      (node (ref "U14") (pin "1") (pinfunction "X1_1") (pintype "passive"))
      (node (ref "Y2") (pin "2") (pinfunction "OSC2_2") (pintype "passive"))
    )
    (net (code "118") (name "Net-(U14-X2)") (class "Default")
      (node (ref "U14") (pin "2") (pinfunction "X2_2") (pintype "passive"))
      (node (ref "Y2") (pin "1") (pinfunction "OSC1_1") (pintype "passive"))
    )
    (net (code "119") (name "Net-(U15-S1)") (class "Default")
      (node (ref "R85") (pin "2") (pinfunction "2_2") (pintype "passive"))
      (node (ref "U15") (pin "19") (pinfunction "S1_19") (pintype "input"))
    )
    (net (code "120") (name "Net-(U15-S2)") (class "Default")
      (node (ref "R86") (pin "2") (pinfunction "2_2") (pintype "passive"))
      (node (ref "U15") (pin "20") (pinfunction "S2_20") (pintype "input"))
    )
    (net (code "121") (name "Net-(U15-S3)") (class "Default")
      (node (ref "R87") (pin "2") (pinfunction "2_2") (pintype "passive"))
      (node (ref "U15") (pin "21") (pinfunction "S3_21") (pintype "input"))
    )
    (net (code "122") (name "Net-(U15-S4)") (class "Default")
      (node (ref "R88") (pin "2") (pinfunction "2_2") (pintype "passive"))
      (node (ref "U15") (pin "22") (pinfunction "S4_22") (pintype "input"))
    )
    (net (code "123") (name "Net-(U15-S5)") (class "Default")
      (node (ref "R89") (pin "2") (pinfunction "2_2") (pintype "passive"))
      (node (ref "U15") (pin "23") (pinfunction "S5_23") (pintype "input"))
    )
    (net (code "124") (name "Net-(U15-S6)") (class "Default")
      (node (ref "R91") (pin "2") (pinfunction "2_2") (pintype "passive"))
      (node (ref "U15") (pin "24") (pinfunction "S6_24") (pintype "input"))
    )
    (net (code "125") (name "Net-(U15-S7)") (class "Default")
      (node (ref "R92") (pin "2") (pinfunction "2_2") (pintype "passive"))
      (node (ref "U15") (pin "25") (pinfunction "S7_25") (pintype "input"))
    )
    (net (code "126") (name "Net-(U15-S8)") (class "Default")
      (node (ref "R93") (pin "2") (pinfunction "2_2") (pintype "passive"))
      (node (ref "U15") (pin "26") (pinfunction "S8_26") (pintype "input"))
    )
    (net (code "127") (name "Net-(U15-S9)") (class "Default")
      (node (ref "R98") (pin "2") (pinfunction "2_2") (pintype "passive"))
      (node (ref "U15") (pin "11") (pinfunction "S9_11") (pintype "input"))
    )
    (net (code "128") (name "Net-(U15-S10)") (class "Default")
      (node (ref "R99") (pin "2") (pinfunction "2_2") (pintype "passive"))
      (node (ref "U15") (pin "10") (pinfunction "S10_10") (pintype "input"))
    )
    (net (code "129") (name "Net-(U15-S11)") (class "Default")
      (node (ref "R102") (pin "2") (pinfunction "2_2") (pintype "passive"))
      (node (ref "U15") (pin "9") (pinfunction "S11_9") (pintype "input"))
    )
    (net (code "130") (name "Net-(U15-S12)") (class "Default")
      (node (ref "R106") (pin "2") (pinfunction "2_2") (pintype "passive"))
      (node (ref "U15") (pin "8") (pinfunction "S12_8") (pintype "input"))
    )
    (net (code "131") (name "Net-(U15-S13)") (class "Default")
      (node (ref "R108") (pin "2") (pinfunction "2_2") (pintype "passive"))
      (node (ref "U15") (pin "7") (pinfunction "S13_7") (pintype "input"))
    )
    (net (code "132") (name "Net-(U15-S14)") (class "Default")
      (node (ref "R109") (pin "2") (pinfunction "2_2") (pintype "passive"))
      (node (ref "U15") (pin "6") (pinfunction "S14_6") (pintype "input"))
    )
    (net (code "133") (name "Net-(U15-S15)") (class "Default")
      (node (ref "R110") (pin "2") (pinfunction "2_2") (pintype "passive"))
      (node (ref "U15") (pin "5") (pinfunction "S15_5") (pintype "input"))
    )
    (net (code "134") (name "Net-(U15-S16)") (class "Default")
      (node (ref "R111") (pin "2") (pinfunction "2_2") (pintype "passive"))
      (node (ref "U15") (pin "4") (pinfunction "S16_4") (pintype "input"))
    )
    (net (code "135") (name "Net-(U17A-IN+)") (class "Default")
      (node (ref "C55") (pin "1") (pinfunction "1_1") (pintype "passive"))
      (node (ref "R101") (pin "2") (pinfunction "2_2") (pintype "passive"))
      (node (ref "U17") (pin "3") (pinfunction "IN+_3") (pintype "input"))
    )
    (net (code "136") (name "Net-(U17A-IN-)") (class "Default")
      (node (ref "C52") (pin "1") (pinfunction "1_1") (pintype "passive"))
      (node (ref "R104") (pin "1") (pinfunction "1_1") (pintype "passive"))
      (node (ref "U17") (pin "1") (pinfunction "OUT_1") (pintype "output"))
      (node (ref "U17") (pin "2") (pinfunction "IN-_2") (pintype "input"))
    )
    (net (code "137") (name "Net-(U17B-IN+)") (class "Default")
      (node (ref "C56") (pin "1") (pinfunction "1_1") (pintype "passive"))
      (node (ref "R105") (pin "2") (pinfunction "2_2") (pintype "passive"))
      (node (ref "U17") (pin "5") (pinfunction "IN+_5") (pintype "input"))
    )
    (net (code "138") (name "Net-(U17B-IN-)") (class "Default")
      (node (ref "C53") (pin "1") (pinfunction "1_1") (pintype "passive"))
      (node (ref "R107") (pin "1") (pinfunction "1_1") (pintype "passive"))
      (node (ref "U17") (pin "6") (pinfunction "IN-_6") (pintype "input"))
      (node (ref "U17") (pin "7") (pinfunction "OUT_7") (pintype "output"))
    )
    (net (code "139") (name "Net-(U17C-IN+)") (class "Default")
      (node (ref "R107") (pin "2") (pinfunction "2_2") (pintype "passive"))
      (node (ref "R112") (pin "2") (pinfunction "2_2") (pintype "passive"))
      (node (ref "U17") (pin "10") (pinfunction "IN+_10") (pintype "input"))
    )
    (net (code "140") (name "Net-(U17C-IN-)") (class "Default")
      (node (ref "R115") (pin "1") (pinfunction "1_1") (pintype "passive"))
      (node (ref "R116") (pin "1") (pinfunction "1_1") (pintype "passive"))
      (node (ref "U17") (pin "9") (pinfunction "IN-_9") (pintype "input"))
    )
    (net (code "141") (name "Net-(U17C-OUT)") (class "Default")
      (node (ref "R115") (pin "2") (pinfunction "2_2") (pintype "passive"))
      (node (ref "U17") (pin "12") (pinfunction "IN+_12") (pintype "input"))
      (node (ref "U17") (pin "8") (pinfunction "OUT_8") (pintype "output"))
    )
    (net (code "142") (name "PGC") (class "Default")
      (node (ref "P9") (pin "5") (pinfunction "5_5") (pintype "passive"))
      (node (ref "R2") (pin "2") (pinfunction "2_2") (pintype "passive"))
      (node (ref "U4") (pin "8") (pinfunction "PGC/EMUC/AN6/OCFA/RB6_8") (pintype "bidirectional"))
    )
    (net (code "143") (name "PGD") (class "Default")
      (node (ref "P9") (pin "4") (pinfunction "4_4") (pintype "passive"))
      (node (ref "U4") (pin "9") (pinfunction "PGD/EMUD/AN7/RB7_9") (pintype "bidirectional"))
    )
    (net (code "144") (name "PIN_EXTRA_3.3V") (class "Default")
      (node (ref "P12") (pin "40") (pinfunction "40_40") (pintype "passive"))
      (node (ref "Q7") (pin "2") (pinfunction "S_2") (pintype "passive"))
      (node (ref "R120") (pin "1") (pinfunction "1_1") (pintype "passive"))
    )
    (net (code "145") (name "PIN_EXTRA_5V") (class "Default")
      (node (ref "Q7") (pin "3") (pinfunction "D_3") (pintype "passive"))
      (node (ref "R121") (pin "1") (pinfunction "1_1") (pintype "passive"))
      (node (ref "U4") (pin "33") (pinfunction "EMUD2/OC2/RD1_33") (pintype "bidirectional"))
    )
    (net (code "146") (name "PIN_PIC_LIBRE") (class "Default")
      (node (ref "P2") (pin "5") (pinfunction "5_5") (pintype "passive"))
      (node (ref "U4") (pin "3") (pinfunction "AN1/VREF-/CN3/RB1_3") (pintype "bidirectional"))
    )
    (net (code "147") (name "PIN_RPi_LIBRE_1") (class "Default")
      (node (ref "P11") (pin "3") (pinfunction "3_3") (pintype "passive"))
      (node (ref "P12") (pin "3") (pinfunction "3_3") (pintype "passive"))
    )
    (net (code "148") (name "PIN_RPi_LIBRE_2") (class "Default")
      (node (ref "P11") (pin "4") (pinfunction "4_4") (pintype "passive"))
      (node (ref "P12") (pin "5") (pinfunction "5_5") (pintype "passive"))
    )
    (net (code "149") (name "PIN_RPi_LIBRE_3") (class "Default")
      (node (ref "P11") (pin "5") (pinfunction "5_5") (pintype "passive"))
      (node (ref "P12") (pin "8") (pinfunction "8_8") (pintype "passive"))
    )
    (net (code "150") (name "PIN_RPi_LIBRE_4") (class "Default")
      (node (ref "P11") (pin "6") (pinfunction "6_6") (pintype "passive"))
      (node (ref "P12") (pin "10") (pinfunction "10_10") (pintype "passive"))
    )
    (net (code "151") (name "PPS_GPS") (class "Default")
      (node (ref "GPS1") (pin "0") (pinfunction "1PPS_0") (pintype "passive"))
      (node (ref "R119") (pin "2") (pinfunction "2_2") (pintype "passive"))
      (node (ref "U4") (pin "17") (pinfunction "INT0/RA11_17") (pintype "bidirectional"))
    )
    (net (code "152") (name "RES1") (class "Default")
      (node (ref "U8") (pin "28") (pinfunction "D_28") (pintype "output"))
      (node (ref "U9") (pin "1") (pinfunction "1_1") (pintype "passive"))
    )
    (net (code "153") (name "RES1B") (class "Default")
      (node (ref "R20") (pin "1") (pinfunction "1_1") (pintype "passive"))
      (node (ref "R21") (pin "1") (pinfunction "1_1") (pintype "passive"))
      (node (ref "R22") (pin "1") (pinfunction "1_1") (pintype "passive"))
      (node (ref "R24") (pin "1") (pinfunction "1_1") (pintype "passive"))
      (node (ref "R25") (pin "1") (pinfunction "1_1") (pintype "passive"))
      (node (ref "R27") (pin "1") (pinfunction "1_1") (pintype "passive"))
      (node (ref "R28") (pin "1") (pinfunction "1_1") (pintype "passive"))
      (node (ref "R29") (pin "1") (pinfunction "1_1") (pintype "passive"))
      (node (ref "R30") (pin "1") (pinfunction "1_1") (pintype "passive"))
      (node (ref "R34") (pin "1") (pinfunction "1_1") (pintype "passive"))
      (node (ref "R37") (pin "1") (pinfunction "1_1") (pintype "passive"))
      (node (ref "R39") (pin "1") (pinfunction "1_1") (pintype "passive"))
      (node (ref "R40") (pin "1") (pinfunction "1_1") (pintype "passive"))
      (node (ref "R41") (pin "1") (pinfunction "1_1") (pintype "passive"))
      (node (ref "R42") (pin "1") (pinfunction "1_1") (pintype "passive"))
      (node (ref "R43") (pin "1") (pinfunction "1_1") (pintype "passive"))
      (node (ref "U9") (pin "8") (pinfunction "8_8") (pintype "passive"))
    )
    (net (code "154") (name "RES2") (class "Default")
      (node (ref "U11") (pin "28") (pinfunction "D_28") (pintype "output"))
      (node (ref "U12") (pin "1") (pinfunction "1_1") (pintype "passive"))
    )
    (net (code "155") (name "RES2B") (class "Default")
      (node (ref "R51") (pin "1") (pinfunction "1_1") (pintype "passive"))
      (node (ref "R52") (pin "1") (pinfunction "1_1") (pintype "passive"))
      (node (ref "R53") (pin "1") (pinfunction "1_1") (pintype "passive"))
      (node (ref "R54") (pin "1") (pinfunction "1_1") (pintype "passive"))
      (node (ref "R55") (pin "1") (pinfunction "1_1") (pintype "passive"))
      (node (ref "R57") (pin "1") (pinfunction "1_1") (pintype "passive"))
      (node (ref "R58") (pin "1") (pinfunction "1_1") (pintype "passive"))
      (node (ref "R59") (pin "1") (pinfunction "1_1") (pintype "passive"))
      (node (ref "R60") (pin "1") (pinfunction "1_1") (pintype "passive"))
      (node (ref "R61") (pin "1") (pinfunction "1_1") (pintype "passive"))
      (node (ref "R64") (pin "1") (pinfunction "1_1") (pintype "passive"))
      (node (ref "R68") (pin "1") (pinfunction "1_1") (pintype "passive"))
      (node (ref "R70") (pin "1") (pinfunction "1_1") (pintype "passive"))
      (node (ref "R71") (pin "1") (pinfunction "1_1") (pintype "passive"))
      (node (ref "R72") (pin "1") (pinfunction "1_1") (pintype "passive"))
      (node (ref "R73") (pin "1") (pinfunction "1_1") (pintype "passive"))
      (node (ref "U12") (pin "8") (pinfunction "8_8") (pintype "passive"))
    )
    (net (code "156") (name "RES3") (class "Default")
      (node (ref "U15") (pin "28") (pinfunction "D_28") (pintype "output"))
      (node (ref "U16") (pin "1") (pinfunction "1_1") (pintype "passive"))
    )
    (net (code "157") (name "RES3B") (class "Default")
      (node (ref "R102") (pin "1") (pinfunction "1_1") (pintype "passive"))
      (node (ref "R106") (pin "1") (pinfunction "1_1") (pintype "passive"))
      (node (ref "R108") (pin "1") (pinfunction "1_1") (pintype "passive"))
      (node (ref "R109") (pin "1") (pinfunction "1_1") (pintype "passive"))
      (node (ref "R110") (pin "1") (pinfunction "1_1") (pintype "passive"))
      (node (ref "R111") (pin "1") (pinfunction "1_1") (pintype "passive"))
      (node (ref "R85") (pin "1") (pinfunction "1_1") (pintype "passive"))
      (node (ref "R86") (pin "1") (pinfunction "1_1") (pintype "passive"))
      (node (ref "R87") (pin "1") (pinfunction "1_1") (pintype "passive"))
      (node (ref "R88") (pin "1") (pinfunction "1_1") (pintype "passive"))
      (node (ref "R89") (pin "1") (pinfunction "1_1") (pintype "passive"))
      (node (ref "R91") (pin "1") (pinfunction "1_1") (pintype "passive"))
      (node (ref "R92") (pin "1") (pinfunction "1_1") (pintype "passive"))
      (node (ref "R93") (pin "1") (pinfunction "1_1") (pintype "passive"))
      (node (ref "R98") (pin "1") (pinfunction "1_1") (pintype "passive"))
      (node (ref "R99") (pin "1") (pinfunction "1_1") (pintype "passive"))
      (node (ref "U16") (pin "8") (pinfunction "8_8") (pintype "passive"))
    )
    (net (code "158") (name "RESET_RPi") (class "Default")
      (node (ref "Q1") (pin "2") (pinfunction "G_2") (pintype "passive"))
      (node (ref "R26") (pin "2") (pinfunction "2_2") (pintype "passive"))
      (node (ref "U4") (pin "30") (pinfunction "RF0_30") (pintype "bidirectional"))
    )
    (net (code "159") (name "RESET_dsPIC_3.3V") (class "Default")
      (node (ref "P12") (pin "38") (pinfunction "38_38") (pintype "passive"))
      (node (ref "Q6") (pin "2") (pinfunction "S_2") (pintype "passive"))
      (node (ref "R96") (pin "1") (pinfunction "1_1") (pintype "passive"))
    )
    (net (code "160") (name "RESET_dsPIC_5V") (class "Default")
      (node (ref "P10") (pin "1") (pinfunction "1_1") (pintype "passive"))
      (node (ref "Q6") (pin "3") (pinfunction "D_3") (pintype "passive"))
      (node (ref "R97") (pin "1") (pinfunction "1_1") (pintype "passive"))
    )
    (net (code "161") (name "RX_GPS") (class "Default")
      (node (ref "GPS1") (pin "3") (pinfunction ">RX_3") (pintype "passive"))
      (node (ref "U4") (pin "15") (pinfunction "EMUD1/SOSCI/T2CK/U1ATX/CN1/RC13_15") (pintype "bidirectional"))
    )
    (net (code "162") (name "Referencia") (class "Default")
      (node (ref "R112") (pin "1") (pinfunction "1_1") (pintype "passive"))
      (node (ref "R44") (pin "1") (pinfunction "1_1") (pintype "passive"))
      (node (ref "R74") (pin "1") (pinfunction "1_1") (pintype "passive"))
      (node (ref "U4") (pin "35") (pinfunction "AN12/RB12_35") (pintype "bidirectional"))
      (node (ref "U7") (pin "1") (pinfunction "OUT_1") (pintype "output"))
      (node (ref "U7") (pin "2") (pinfunction "IN-_2") (pintype "input"))
    )
    (net (code "163") (name "SCK_3.3V") (class "Default")
      (node (ref "P12") (pin "23") (pinfunction "23_23") (pintype "passive"))
      (node (ref "Q5") (pin "2") (pinfunction "S_2") (pintype "passive"))
      (node (ref "R94") (pin "1") (pinfunction "1_1") (pintype "passive"))
    )
    (net (code "164") (name "SCK_5V") (class "Default")
      (node (ref "Q5") (pin "3") (pinfunction "D_3") (pintype "passive"))
      (node (ref "R95") (pin "1") (pinfunction "1_1") (pintype "passive"))
      (node (ref "U4") (pin "24") (pinfunction "EMUC3/SCK1/RF6_24") (pintype "bidirectional"))
    )
    (net (code "165") (name "SCL_DS1307") (class "Default")
      (node (ref "R79") (pin "2") (pinfunction "2_2") (pintype "passive"))
      (node (ref "U14") (pin "6") (pinfunction "SCL_6") (pintype "bidirectional"))
      (node (ref "U4") (pin "22") (pinfunction "RD2_22") (pintype "bidirectional"))
    )
    (net (code "166") (name "SDA_DS1307") (class "Default")
      (node (ref "R80") (pin "2") (pinfunction "2_2") (pintype "passive"))
      (node (ref "U14") (pin "5") (pinfunction "SDA_5") (pintype "bidirectional"))
      (node (ref "U4") (pin "23") (pinfunction "IC1/INT1/RD8_23") (pintype "bidirectional"))
    )
    (net (code "167") (name "Señal1") (class "Default")
      (node (ref "U10") (pin "13") (pinfunction "IN-_13") (pintype "input"))
      (node (ref "U10") (pin "14") (pinfunction "OUT_14") (pintype "output"))
      (node (ref "U4") (pin "36") (pinfunction "AN11/RB11_36") (pintype "bidirectional"))
    )
    (net (code "168") (name "Señal2") (class "Default")
      (node (ref "U13") (pin "13") (pinfunction "IN-_13") (pintype "input"))
      (node (ref "U13") (pin "14") (pinfunction "OUT_14") (pintype "output"))
      (node (ref "U4") (pin "37") (pinfunction "AN10/RB10_37") (pintype "bidirectional"))
    )
    (net (code "169") (name "Señal3") (class "Default")
      (node (ref "U17") (pin "13") (pinfunction "IN-_13") (pintype "input"))
      (node (ref "U17") (pin "14") (pinfunction "OUT_14") (pintype "output"))
      (node (ref "U4") (pin "38") (pinfunction "AN9/RB9_38") (pintype "bidirectional"))
    )
    (net (code "170") (name "TX_GPS_3.3V") (class "Default")
      (node (ref "GPS1") (pin "4") (pinfunction "<TX_4") (pintype "passive"))
      (node (ref "Q2") (pin "2") (pinfunction "S_2") (pintype "passive"))
      (node (ref "R49") (pin "1") (pinfunction "1_1") (pintype "passive"))
    )
    (net (code "171") (name "TX_GPS_5V") (class "Default")
      (node (ref "Q2") (pin "3") (pinfunction "D_3") (pintype "passive"))
      (node (ref "R50") (pin "1") (pinfunction "1_1") (pintype "passive"))
      (node (ref "U4") (pin "16") (pinfunction "EMUC1/SOSCO/T1CK/U1ARX/CN0/RC14_16") (pintype "bidirectional"))
    )
    (net (code "172") (name "U2RX") (class "Default")
      (node (ref "P2") (pin "3") (pinfunction "3_3") (pintype "passive"))
      (node (ref "U4") (pin "28") (pinfunction "U2RX/CN17/RF4_28") (pintype "bidirectional"))
    )
    (net (code "173") (name "U2TX") (class "Default")
      (node (ref "P2") (pin "4") (pinfunction "4_4") (pintype "passive"))
      (node (ref "U4") (pin "27") (pinfunction "U2TX/CN18/RF5_27") (pintype "bidirectional"))
    )
    (net (code "174") (name "unconnected-(GPS1-3.3V-Pad8)") (class "Default")
      (node (ref "GPS1") (pin "8") (pinfunction "3.3V_8") (pintype "passive"))
    )
    (net (code "175") (name "unconnected-(GPS1-FIX-Pad5)") (class "Default")
      (node (ref "GPS1") (pin "5") (pinfunction "FIX_5") (pintype "passive"))
    )
    (net (code "176") (name "unconnected-(GPS1-VBAT-Pad6)") (class "Default")
      (node (ref "GPS1") (pin "6") (pinfunction "VBAT_6") (pintype "passive"))
    )
    (net (code "177") (name "unconnected-(P3-Pad1)") (class "Default")
      (node (ref "P3") (pin "1") (pinfunction "1_1") (pintype "passive"))
    )
    (net (code "178") (name "unconnected-(P4-Pad1)") (class "Default")
      (node (ref "P4") (pin "1") (pinfunction "1_1") (pintype "passive"))
    )
    (net (code "179") (name "unconnected-(P8-Pad3)") (class "Default")
      (node (ref "P8") (pin "3") (pinfunction "3_3") (pintype "passive"))
    )
    (net (code "180") (name "unconnected-(P9-Pad6)") (class "Default")
      (node (ref "P9") (pin "6") (pinfunction "6_6") (pintype "passive"))
    )
    (net (code "181") (name "unconnected-(P10-Pad3)") (class "Default")
      (node (ref "P10") (pin "3") (pinfunction "3_3") (pintype "passive"))
    )
    (net (code "182") (name "unconnected-(P12-Pad7)") (class "Default")
      (node (ref "P12") (pin "7") (pinfunction "7_7") (pintype "passive"))
    )
    (net (code "183") (name "unconnected-(P12-Pad12)") (class "Default")
      (node (ref "P12") (pin "12") (pinfunction "12_12") (pintype "passive"))
    )
    (net (code "184") (name "unconnected-(P12-Pad13)") (class "Default")
      (node (ref "P12") (pin "13") (pinfunction "13_13") (pintype "passive"))
    )
    (net (code "185") (name "unconnected-(P12-Pad15)") (class "Default")
      (node (ref "P12") (pin "15") (pinfunction "15_15") (pintype "passive"))
    )
    (net (code "186") (name "unconnected-(P12-Pad16)") (class "Default")
      (node (ref "P12") (pin "16") (pinfunction "16_16") (pintype "passive"))
    )
    (net (code "187") (name "unconnected-(P12-Pad18)") (class "Default")
      (node (ref "P12") (pin "18") (pinfunction "18_18") (pintype "passive"))
    )
    (net (code "188") (name "unconnected-(P12-Pad22)") (class "Default")
      (node (ref "P12") (pin "22") (pinfunction "22_22") (pintype "passive"))
    )
    (net (code "189") (name "unconnected-(P12-Pad26)") (class "Default")
      (node (ref "P12") (pin "26") (pinfunction "26_26") (pintype "passive"))
    )
    (net (code "190") (name "unconnected-(P12-Pad27)") (class "Default")
      (node (ref "P12") (pin "27") (pinfunction "27_27") (pintype "passive"))
    )
    (net (code "191") (name "unconnected-(P12-Pad28)") (class "Default")
      (node (ref "P12") (pin "28") (pinfunction "28_28") (pintype "passive"))
    )
    (net (code "192") (name "unconnected-(P12-Pad29)") (class "Default")
      (node (ref "P12") (pin "29") (pinfunction "29_29") (pintype "passive"))
    )
    (net (code "193") (name "unconnected-(P12-Pad31)") (class "Default")
      (node (ref "P12") (pin "31") (pinfunction "31_31") (pintype "passive"))
    )
    (net (code "194") (name "unconnected-(P12-Pad33)") (class "Default")
      (node (ref "P12") (pin "33") (pinfunction "33_33") (pintype "passive"))
    )
    (net (code "195") (name "unconnected-(P12-Pad35)") (class "Default")
      (node (ref "P12") (pin "35") (pinfunction "35_35") (pintype "passive"))
    )
    (net (code "196") (name "unconnected-(P12-Pad37)") (class "Default")
      (node (ref "P12") (pin "37") (pinfunction "37_37") (pintype "passive"))
    )
    (net (code "197") (name "unconnected-(R8-BOT-Pad2)") (class "Default")
      (node (ref "R8") (pin "2") (pinfunction "BOT_2") (pintype "passive"))
    )
    (net (code "198") (name "unconnected-(R9-BOT-Pad2)") (class "Default")
      (node (ref "R9") (pin "2") (pinfunction "BOT_2") (pintype "passive"))
    )
    (net (code "199") (name "unconnected-(U2-NC-Pad1)") (class "Default")
      (node (ref "U2") (pin "1") (pinfunction "NC_1") (pintype "passive"))
    )
    (net (code "200") (name "unconnected-(U2-NC-Pad6)") (class "Default")
      (node (ref "U2") (pin "6") (pinfunction "NC_6") (pintype "passive"))
    )
    (net (code "201") (name "unconnected-(U2-OSC-Pad7)") (class "Default")
      (node (ref "U2") (pin "7") (pinfunction "OSC_7") (pintype "input"))
    )
    (net (code "202") (name "unconnected-(U3-NC-Pad1)") (class "Default")
      (node (ref "U3") (pin "1") (pinfunction "NC_1") (pintype "passive"))
    )
    (net (code "203") (name "unconnected-(U3-NC-Pad6)") (class "Default")
      (node (ref "U3") (pin "6") (pinfunction "NC_6") (pintype "passive"))
    )
    (net (code "204") (name "unconnected-(U3-OSC-Pad7)") (class "Default")
      (node (ref "U3") (pin "7") (pinfunction "OSC_7") (pintype "input"))
    )
    (net (code "205") (name "unconnected-(U4-AN8{slash}RB8-Pad10)") (class "Default")
      (node (ref "U4") (pin "10") (pinfunction "AN8/RB8_10") (pintype "bidirectional"))
    )
    (net (code "206") (name "unconnected-(U8-NC-Pad2)") (class "Default")
      (node (ref "U8") (pin "2") (pinfunction "NC_2") (pintype "passive"))
    )
    (net (code "207") (name "unconnected-(U8-NC-Pad3)") (class "Default")
      (node (ref "U8") (pin "3") (pinfunction "NC_3") (pintype "passive"))
    )
    (net (code "208") (name "unconnected-(U8-NC-Pad13)") (class "Default")
      (node (ref "U8") (pin "13") (pinfunction "NC_13") (pintype "passive"))
    )
    (net (code "209") (name "unconnected-(U10B-V+-Pad4)") (class "Default")
      (node (ref "U10") (pin "4") (pinfunction "V+_4") (pintype "power_in"))
    )
    (net (code "210") (name "unconnected-(U10B-V--Pad11)") (class "Default")
      (node (ref "U10") (pin "11") (pinfunction "V-_11") (pintype "power_in"))
    )
    (net (code "211") (name "unconnected-(U10C-V+-Pad4)") (class "Default")
      (node (ref "U10") (pin "4") (pinfunction "V+_4") (pintype "power_in"))
    )
    (net (code "212") (name "unconnected-(U10C-V--Pad11)") (class "Default")
      (node (ref "U10") (pin "11") (pinfunction "V-_11") (pintype "power_in"))
    )
    (net (code "213") (name "unconnected-(U10D-V+-Pad4)") (class "Default")
      (node (ref "U10") (pin "4") (pinfunction "V+_4") (pintype "power_in"))
    )
    (net (code "214") (name "unconnected-(U10D-V--Pad11)") (class "Default")
      (node (ref "U10") (pin "11") (pinfunction "V-_11") (pintype "power_in"))
    )
    (net (code "215") (name "unconnected-(U11-NC-Pad2)") (class "Default")
      (node (ref "U11") (pin "2") (pinfunction "NC_2") (pintype "passive"))
    )
    (net (code "216") (name "unconnected-(U11-NC-Pad3)") (class "Default")
      (node (ref "U11") (pin "3") (pinfunction "NC_3") (pintype "passive"))
    )
    (net (code "217") (name "unconnected-(U11-NC-Pad13)") (class "Default")
      (node (ref "U11") (pin "13") (pinfunction "NC_13") (pintype "passive"))
    )
    (net (code "218") (name "unconnected-(U13B-V+-Pad4)") (class "Default")
      (node (ref "U13") (pin "4") (pinfunction "V+_4") (pintype "power_in"))
    )
    (net (code "219") (name "unconnected-(U13B-V--Pad11)") (class "Default")
      (node (ref "U13") (pin "11") (pinfunction "V-_11") (pintype "power_in"))
    )
    (net (code "220") (name "unconnected-(U13C-V+-Pad4)") (class "Default")
      (node (ref "U13") (pin "4") (pinfunction "V+_4") (pintype "power_in"))
    )
    (net (code "221") (name "unconnected-(U13C-V--Pad11)") (class "Default")
      (node (ref "U13") (pin "11") (pinfunction "V-_11") (pintype "power_in"))
    )
    (net (code "222") (name "unconnected-(U13D-V+-Pad4)") (class "Default")
      (node (ref "U13") (pin "4") (pinfunction "V+_4") (pintype "power_in"))
    )
    (net (code "223") (name "unconnected-(U13D-V--Pad11)") (class "Default")
      (node (ref "U13") (pin "11") (pinfunction "V-_11") (pintype "power_in"))
    )
    (net (code "224") (name "unconnected-(U15-NC-Pad2)") (class "Default")
      (node (ref "U15") (pin "2") (pinfunction "NC_2") (pintype "passive"))
    )
    (net (code "225") (name "unconnected-(U15-NC-Pad3)") (class "Default")
      (node (ref "U15") (pin "3") (pinfunction "NC_3") (pintype "passive"))
    )
    (net (code "226") (name "unconnected-(U15-NC-Pad13)") (class "Default")
      (node (ref "U15") (pin "13") (pinfunction "NC_13") (pintype "passive"))
    )
    (net (code "227") (name "unconnected-(U17B-V+-Pad4)") (class "Default")
      (node (ref "U17") (pin "4") (pinfunction "V+_4") (pintype "power_in"))
    )
    (net (code "228") (name "unconnected-(U17B-V--Pad11)") (class "Default")
      (node (ref "U17") (pin "11") (pinfunction "V-_11") (pintype "power_in"))
    )
    (net (code "229") (name "unconnected-(U17C-V+-Pad4)") (class "Default")
      (node (ref "U17") (pin "4") (pinfunction "V+_4") (pintype "power_in"))
    )
    (net (code "230") (name "unconnected-(U17C-V--Pad11)") (class "Default")
      (node (ref "U17") (pin "11") (pinfunction "V-_11") (pintype "power_in"))
    )
    (net (code "231") (name "unconnected-(U17D-V+-Pad4)") (class "Default")
      (node (ref "U17") (pin "4") (pinfunction "V+_4") (pintype "power_in"))
    )
    (net (code "232") (name "unconnected-(U17D-V--Pad11)") (class "Default")
      (node (ref "U17") (pin "11") (pinfunction "V-_11") (pintype "power_in"))
    )
  )
)
